# Chestnut_V2_0.net
KiCad netlist of a schematic drawn in EAGLE
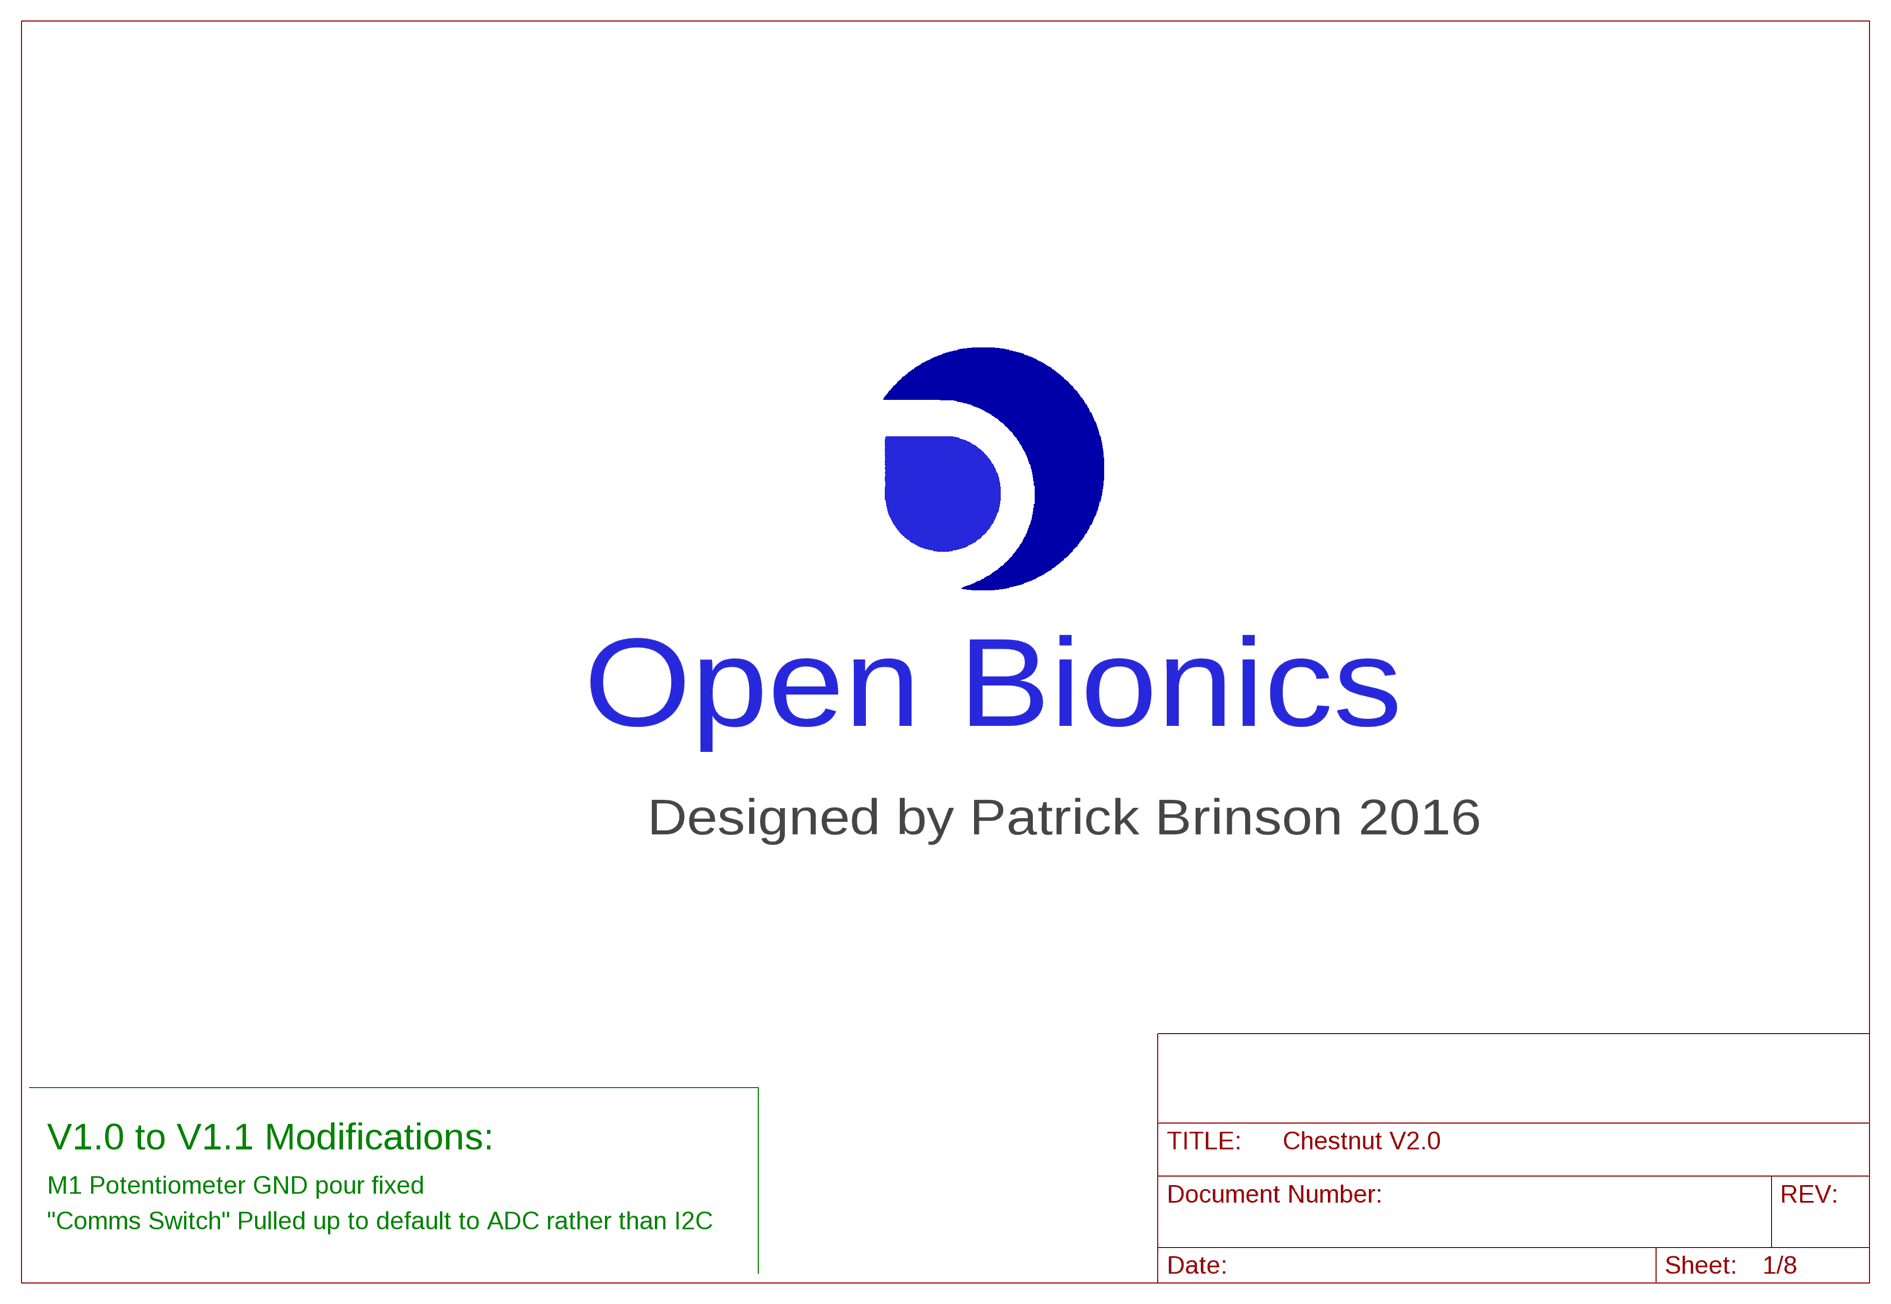
[diagram p0: schematic, sheet 1]
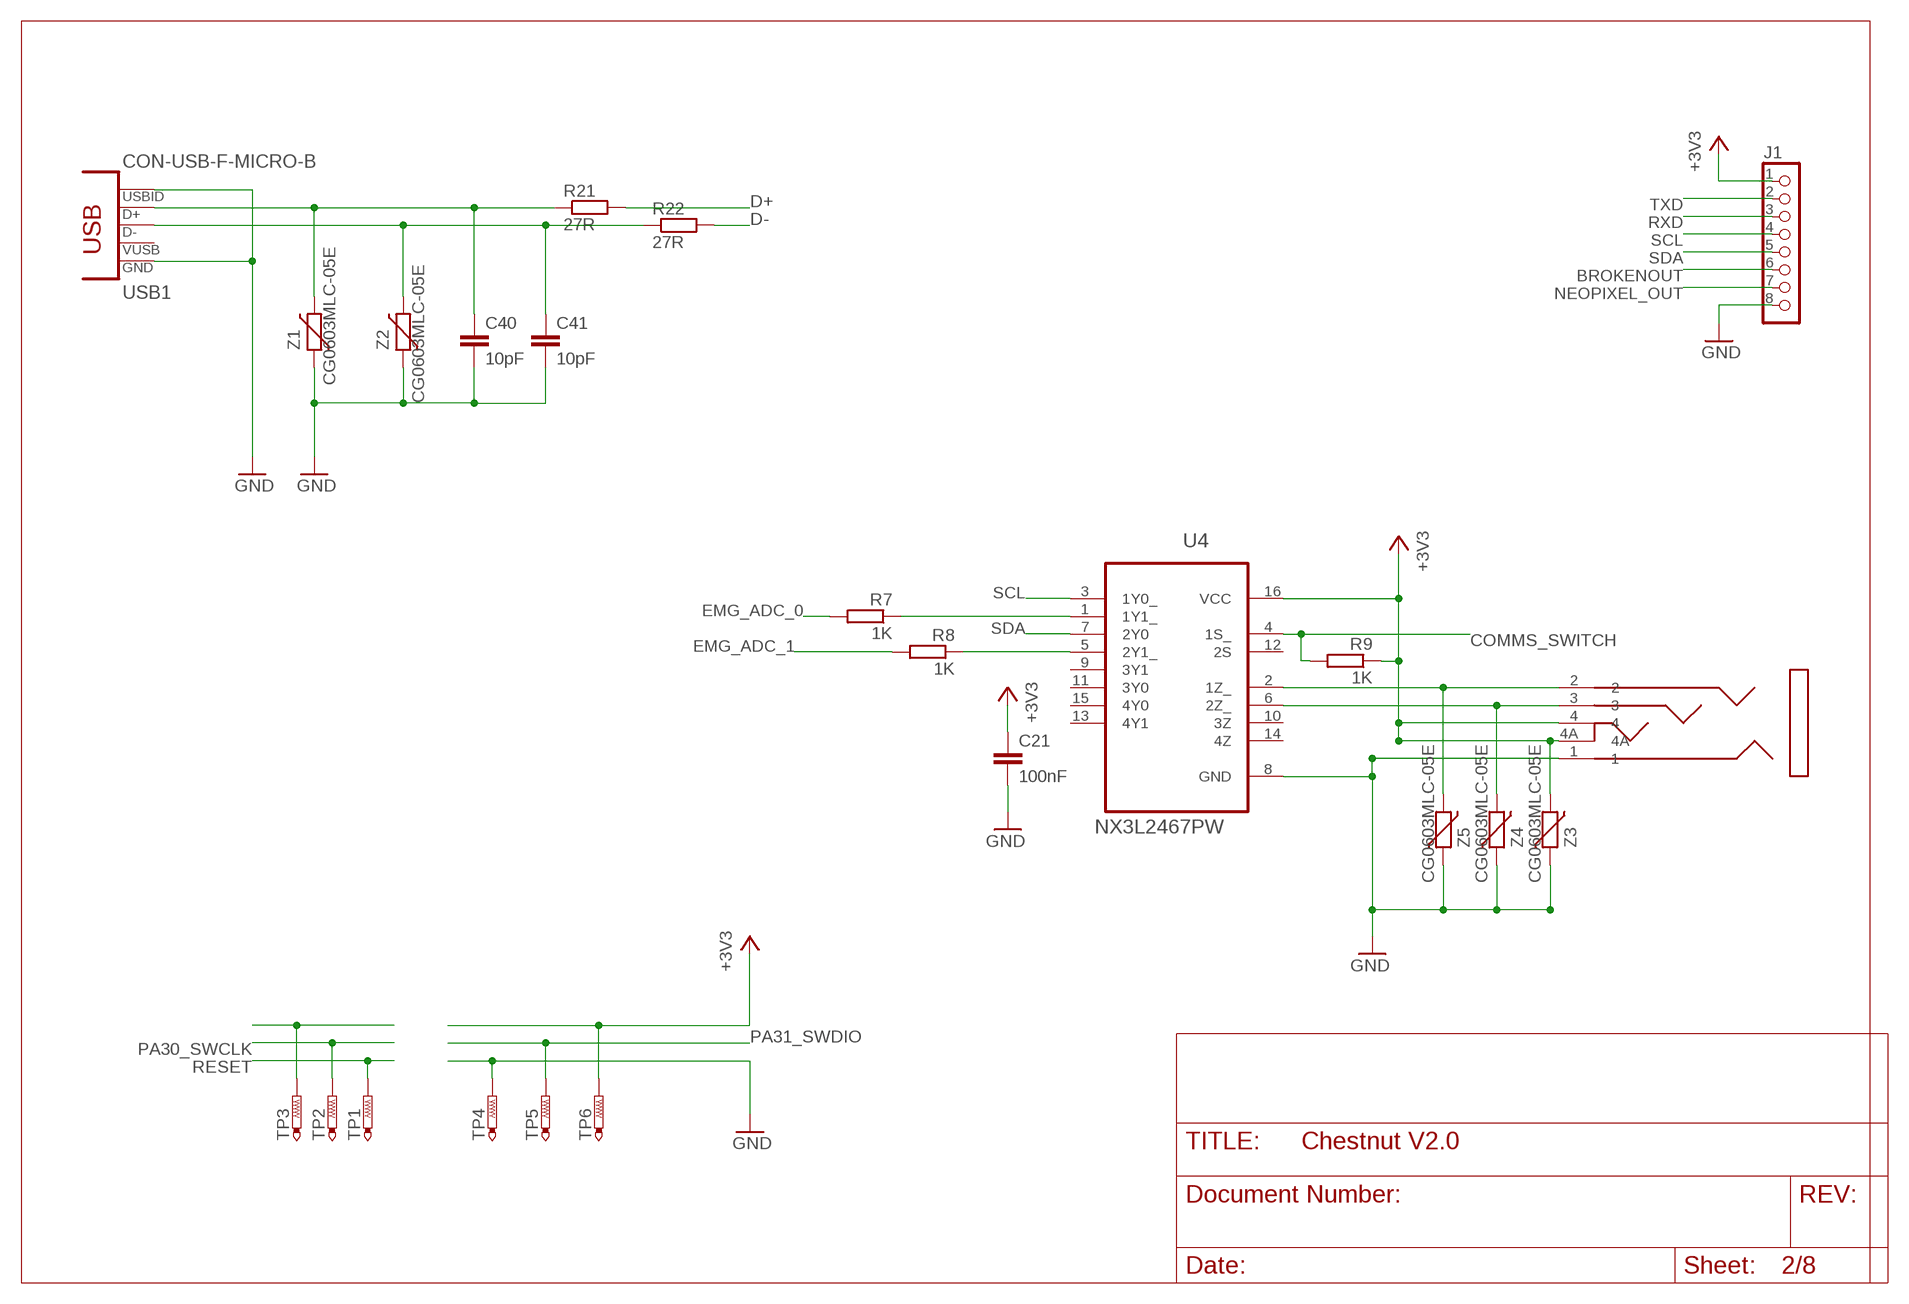
[diagram p1: schematic, sheet 2]
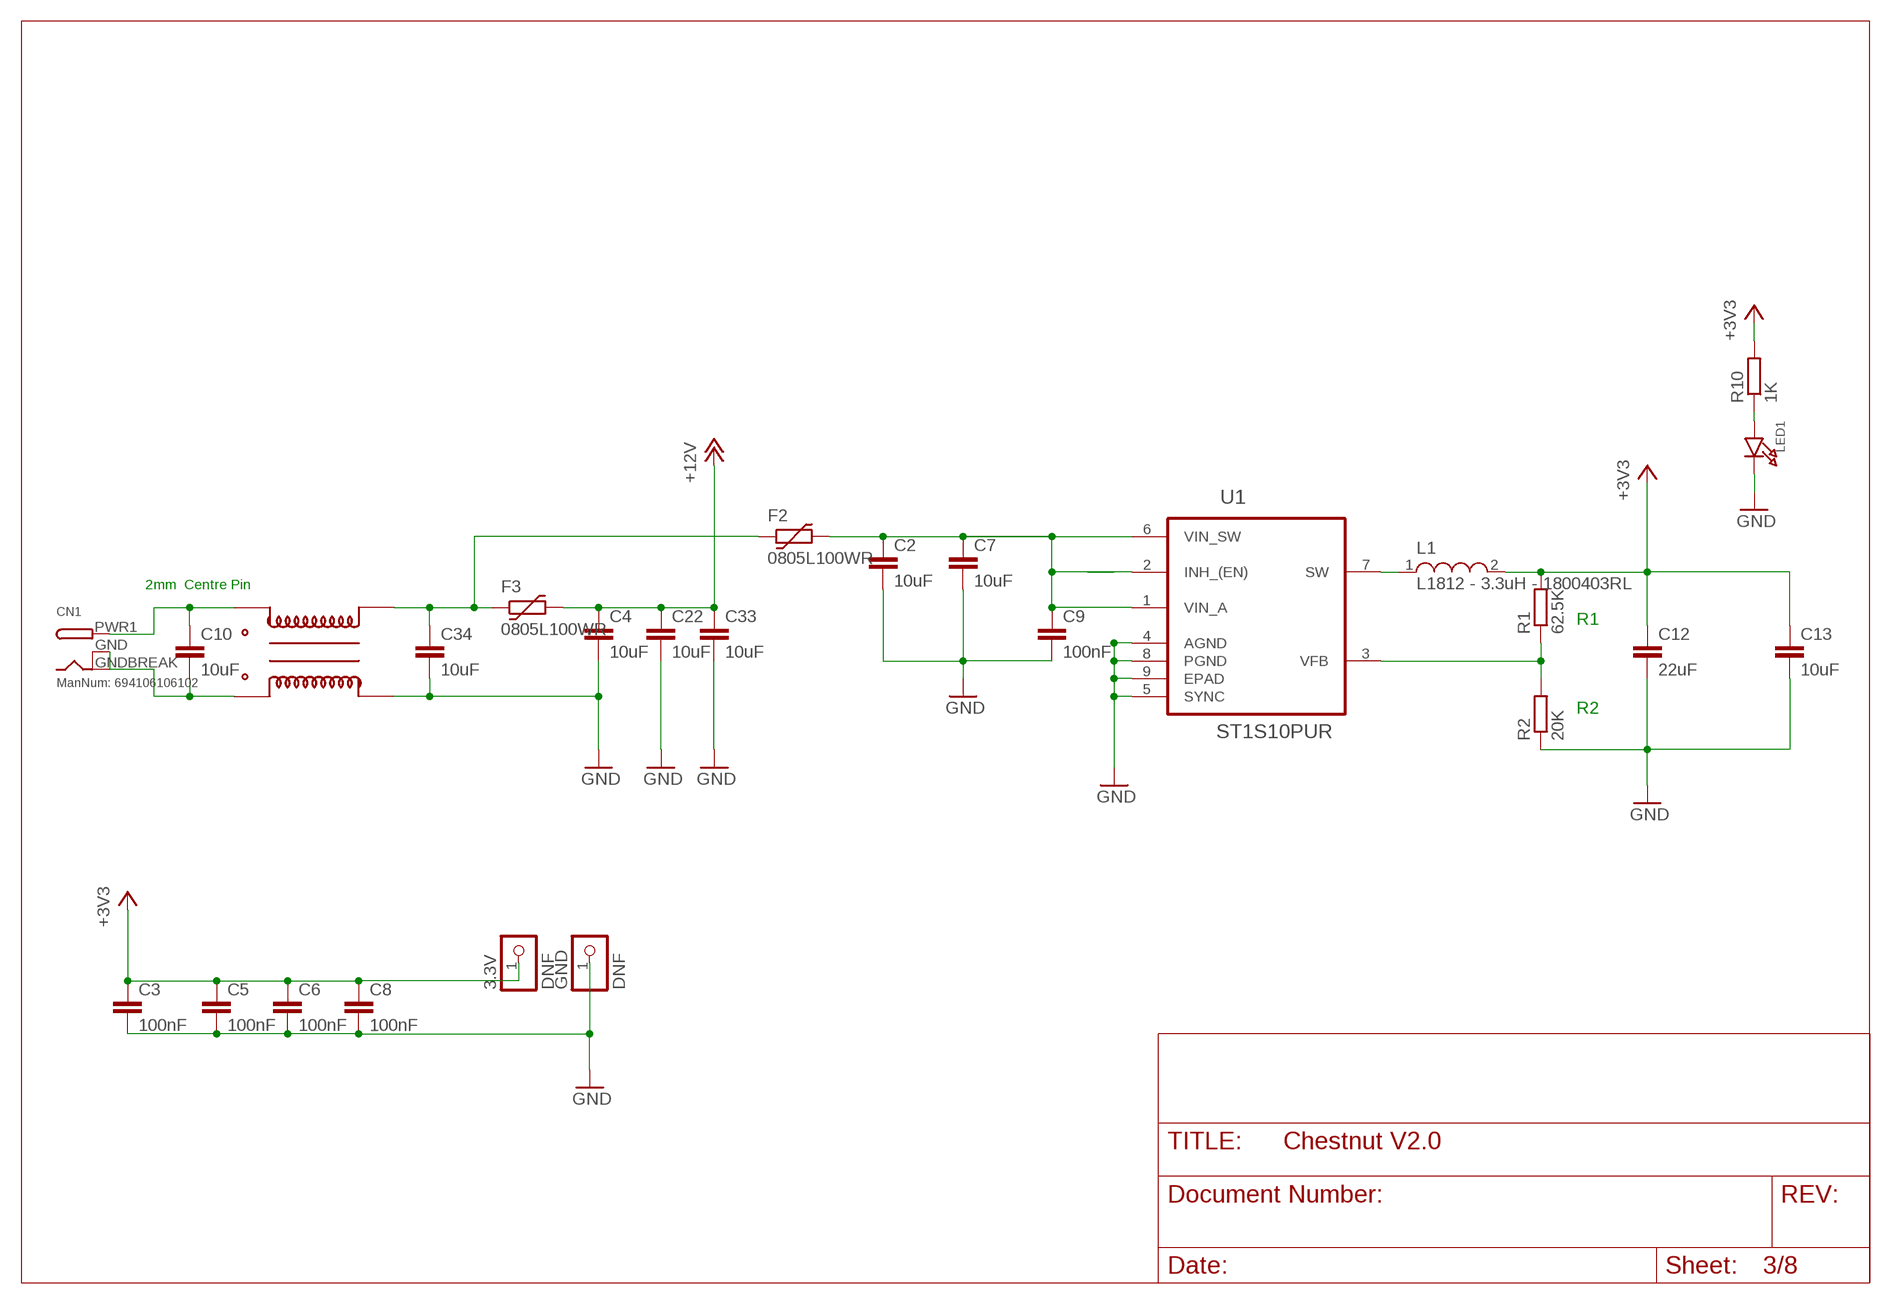
[diagram p2: schematic, sheet 3]
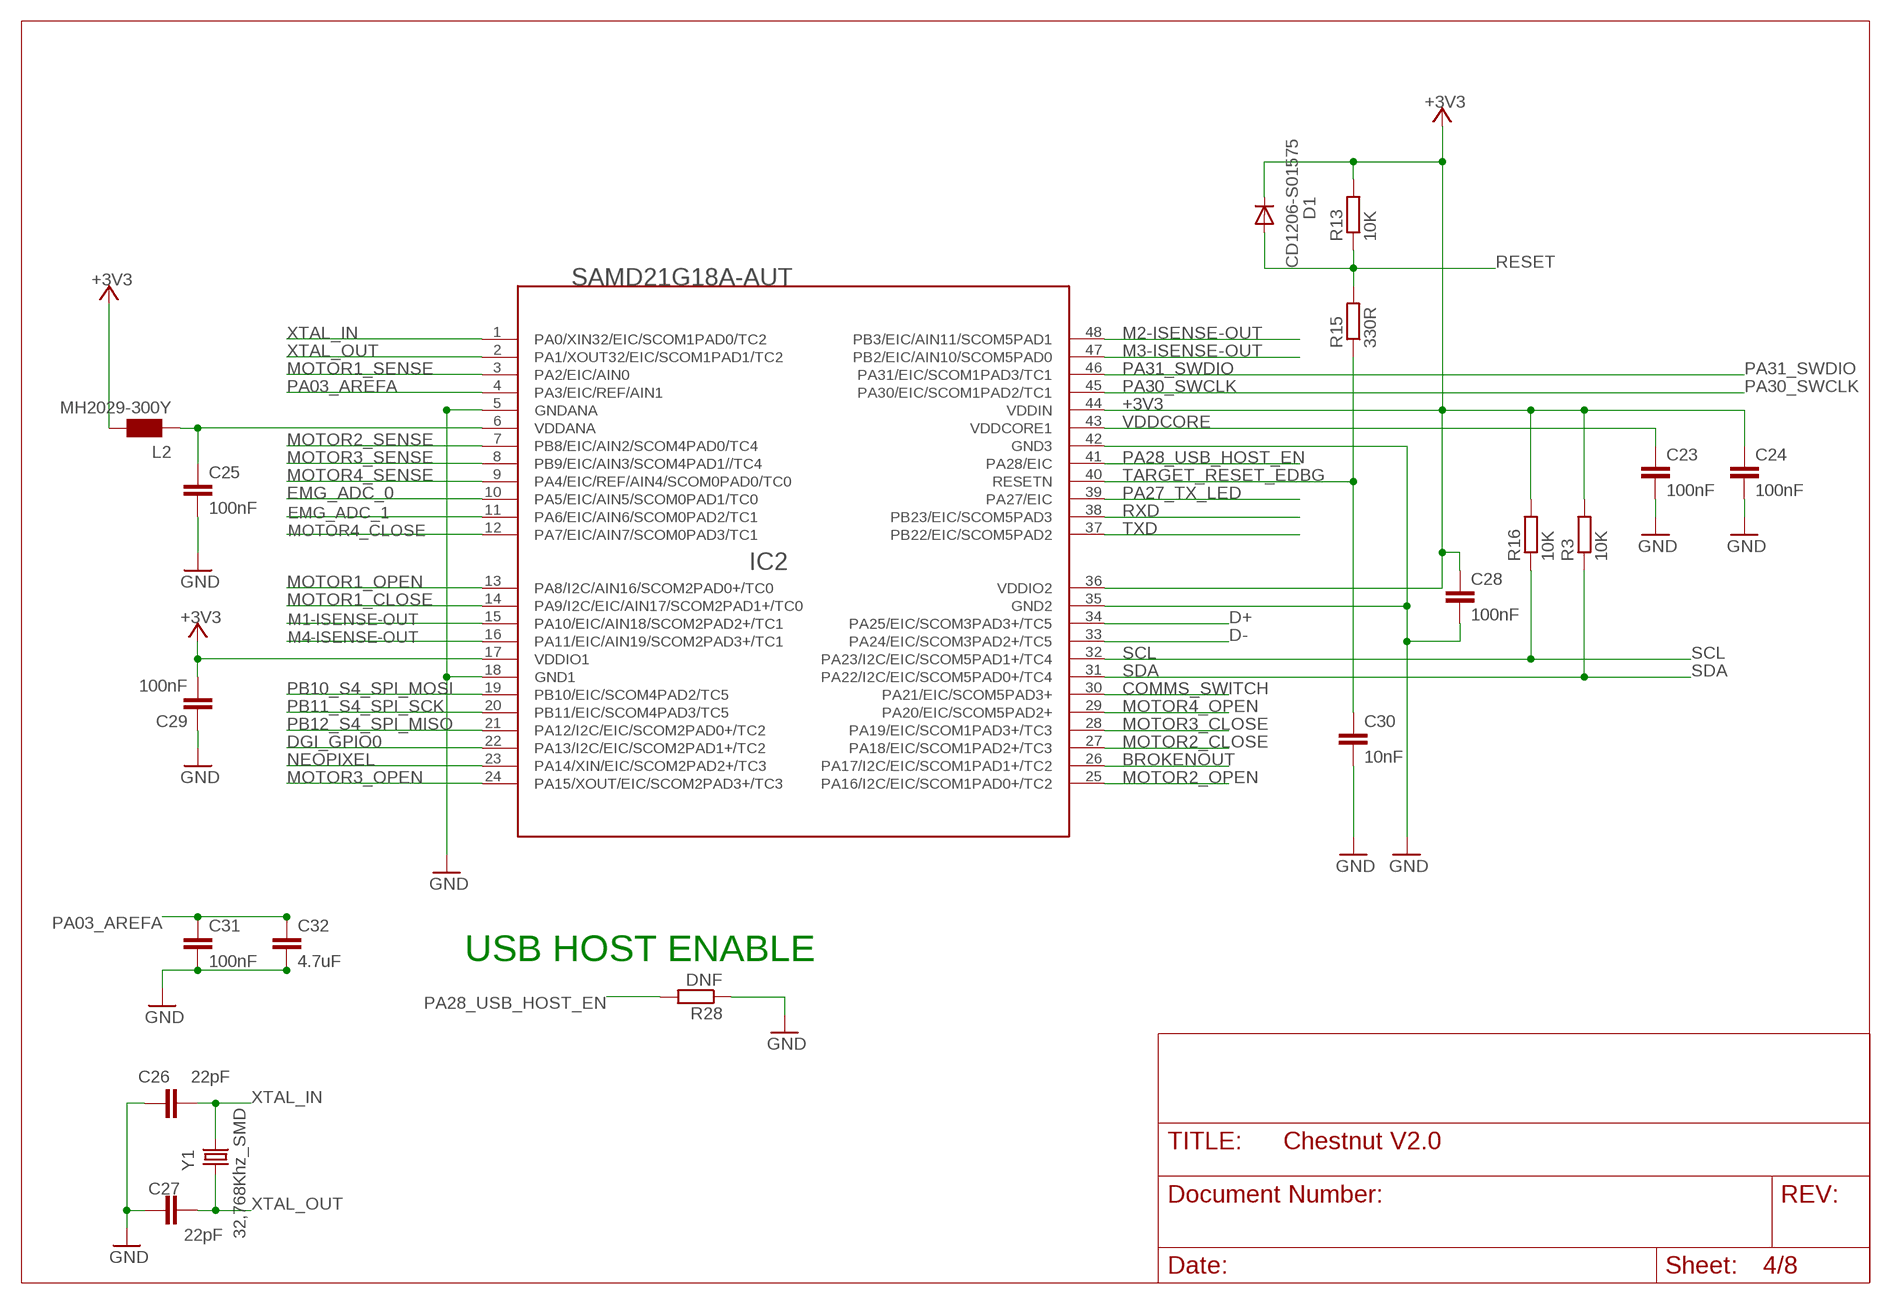
[diagram p3: schematic, sheet 4]
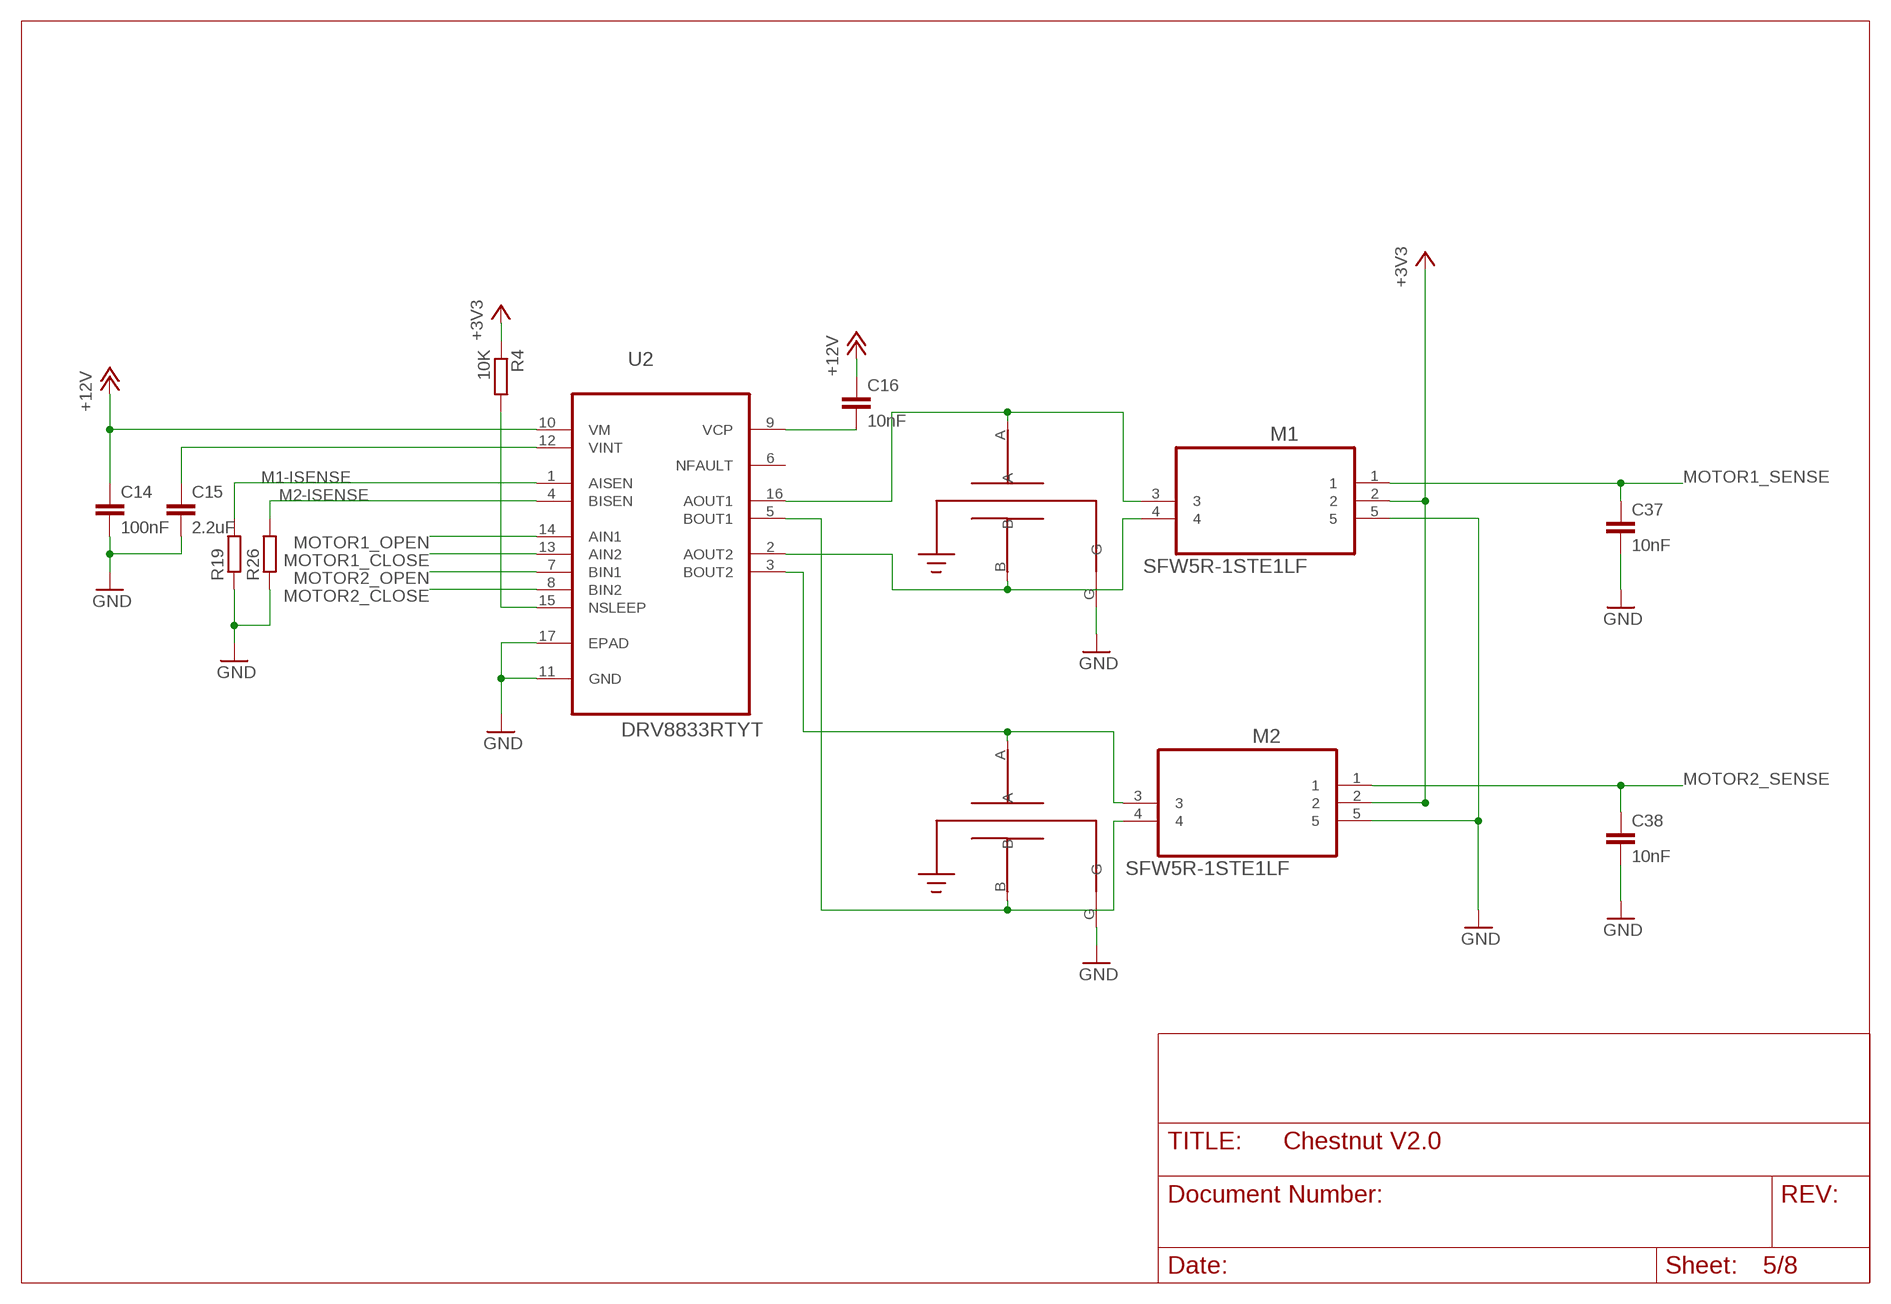
[diagram p4: schematic, sheet 5]
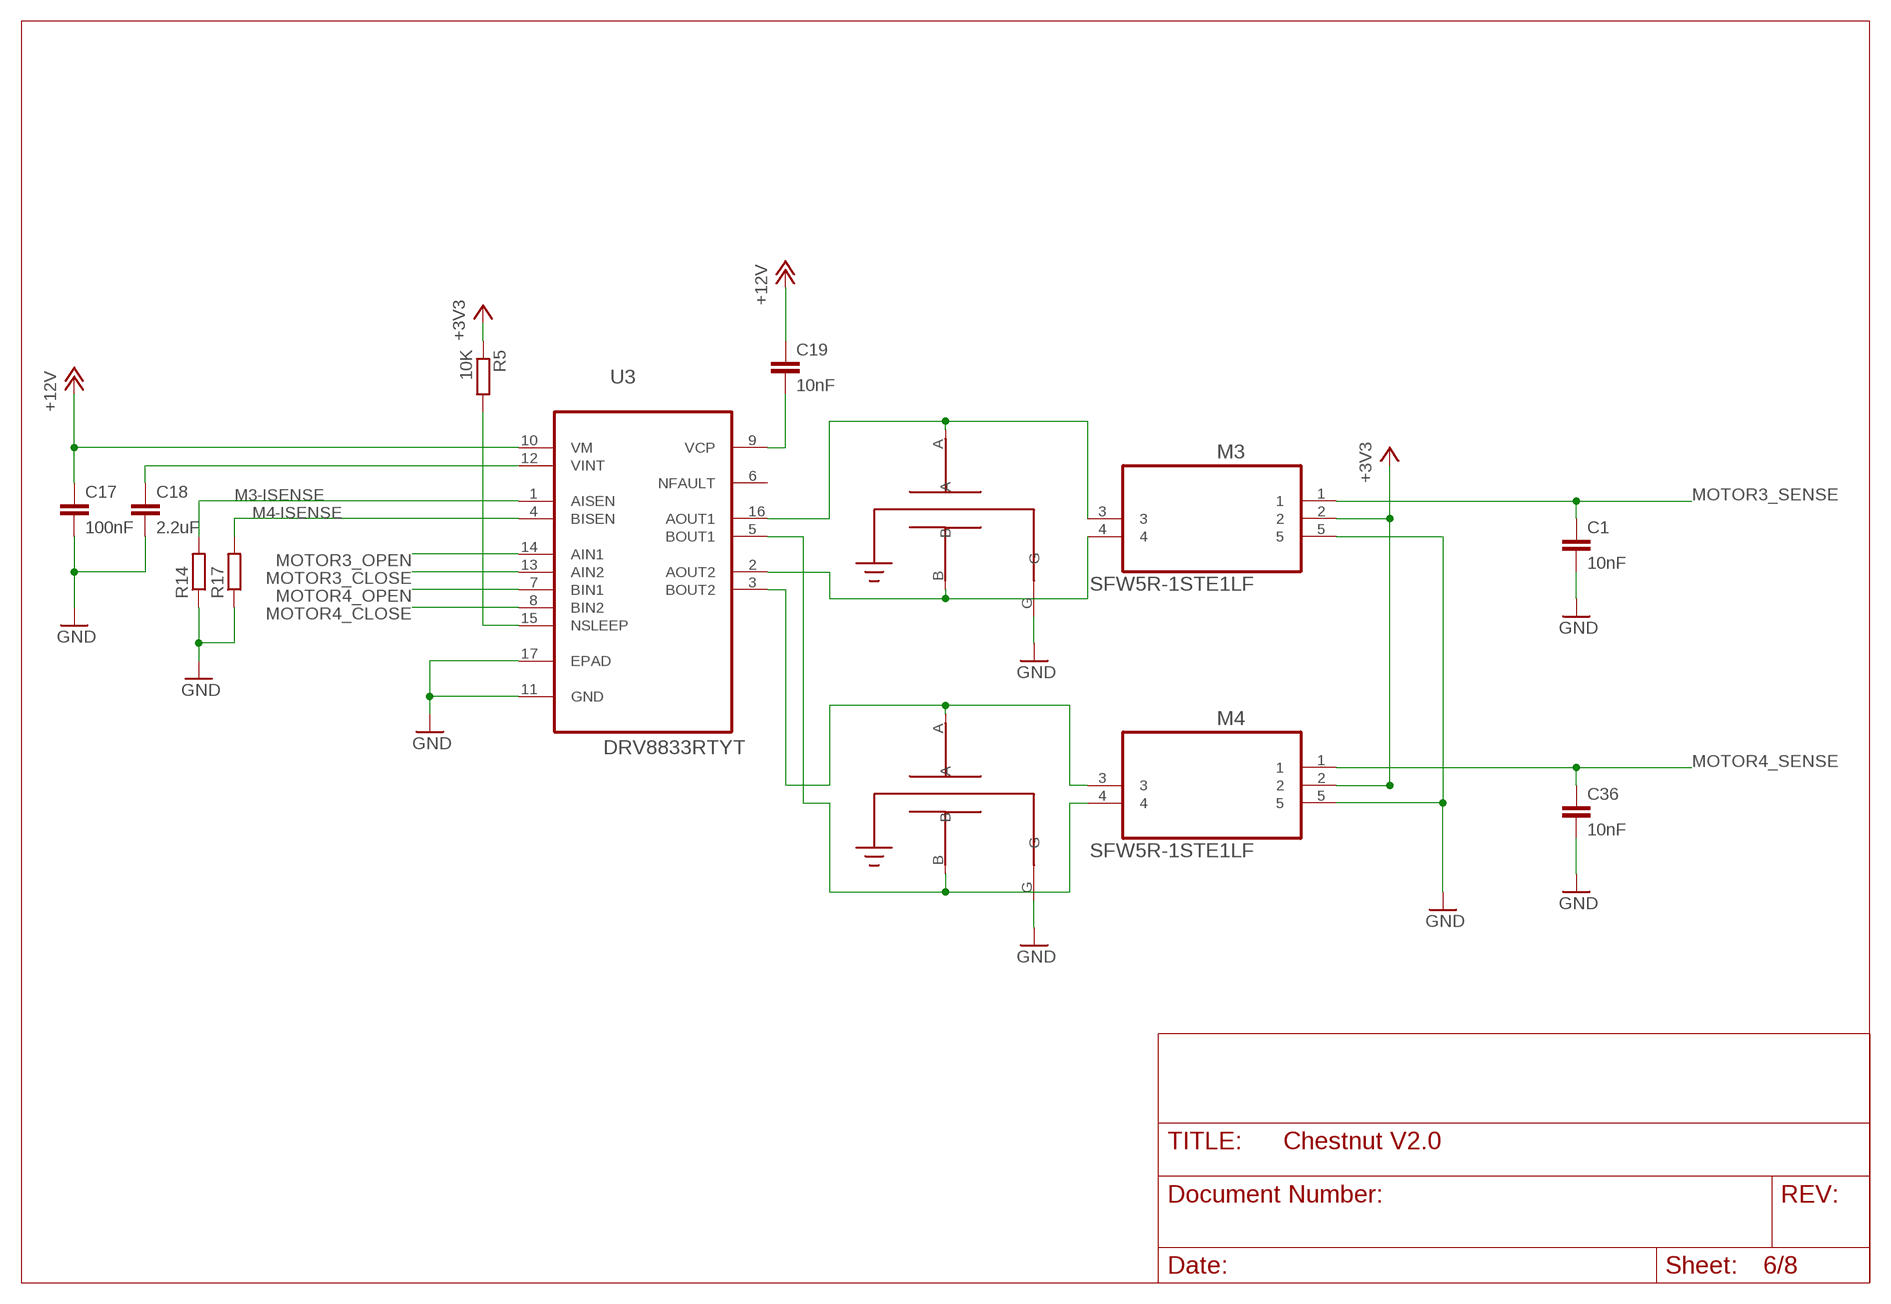
[diagram p5: schematic, sheet 6]
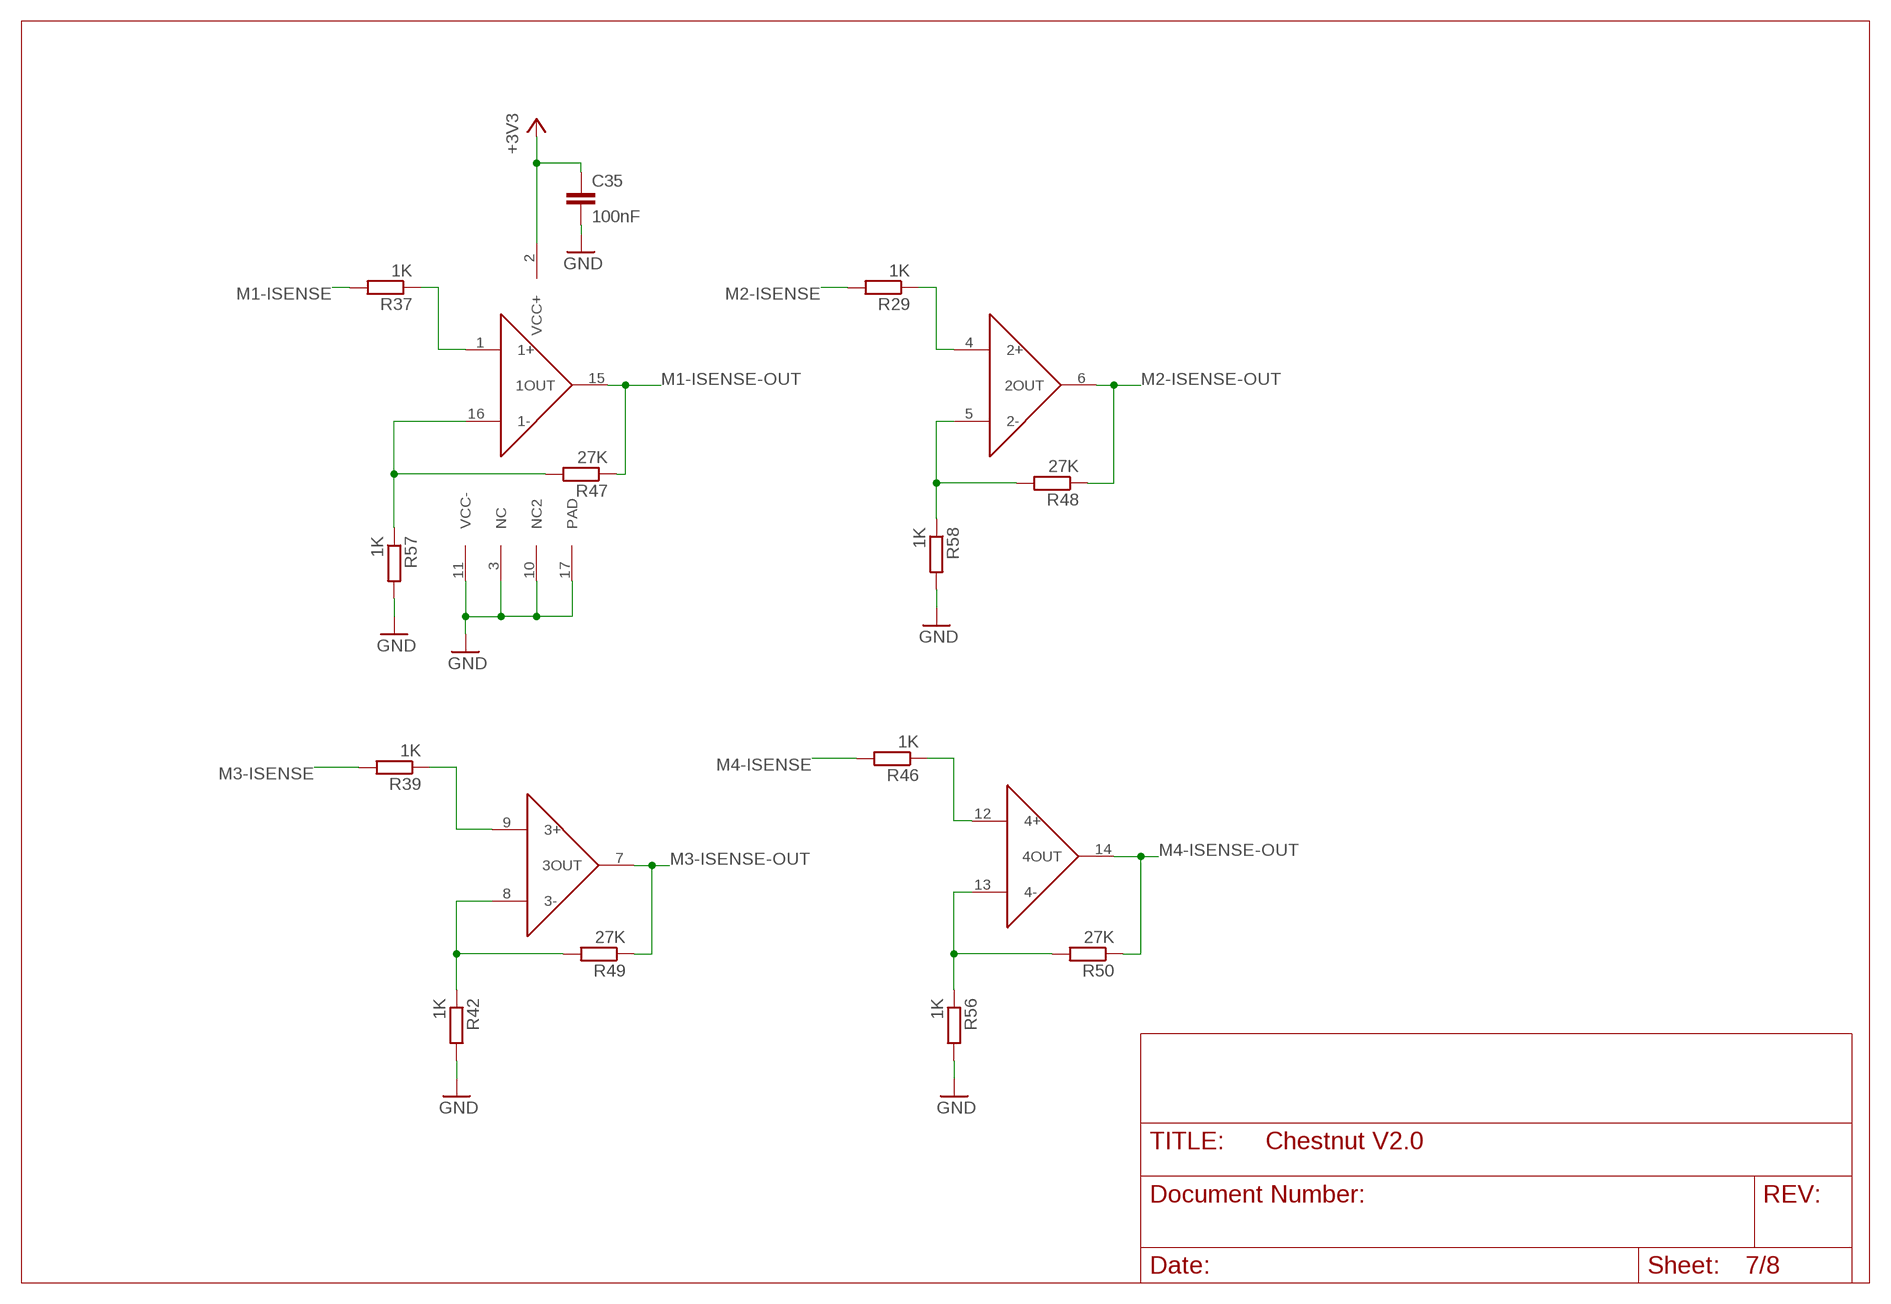
[diagram p6: schematic, sheet 7]
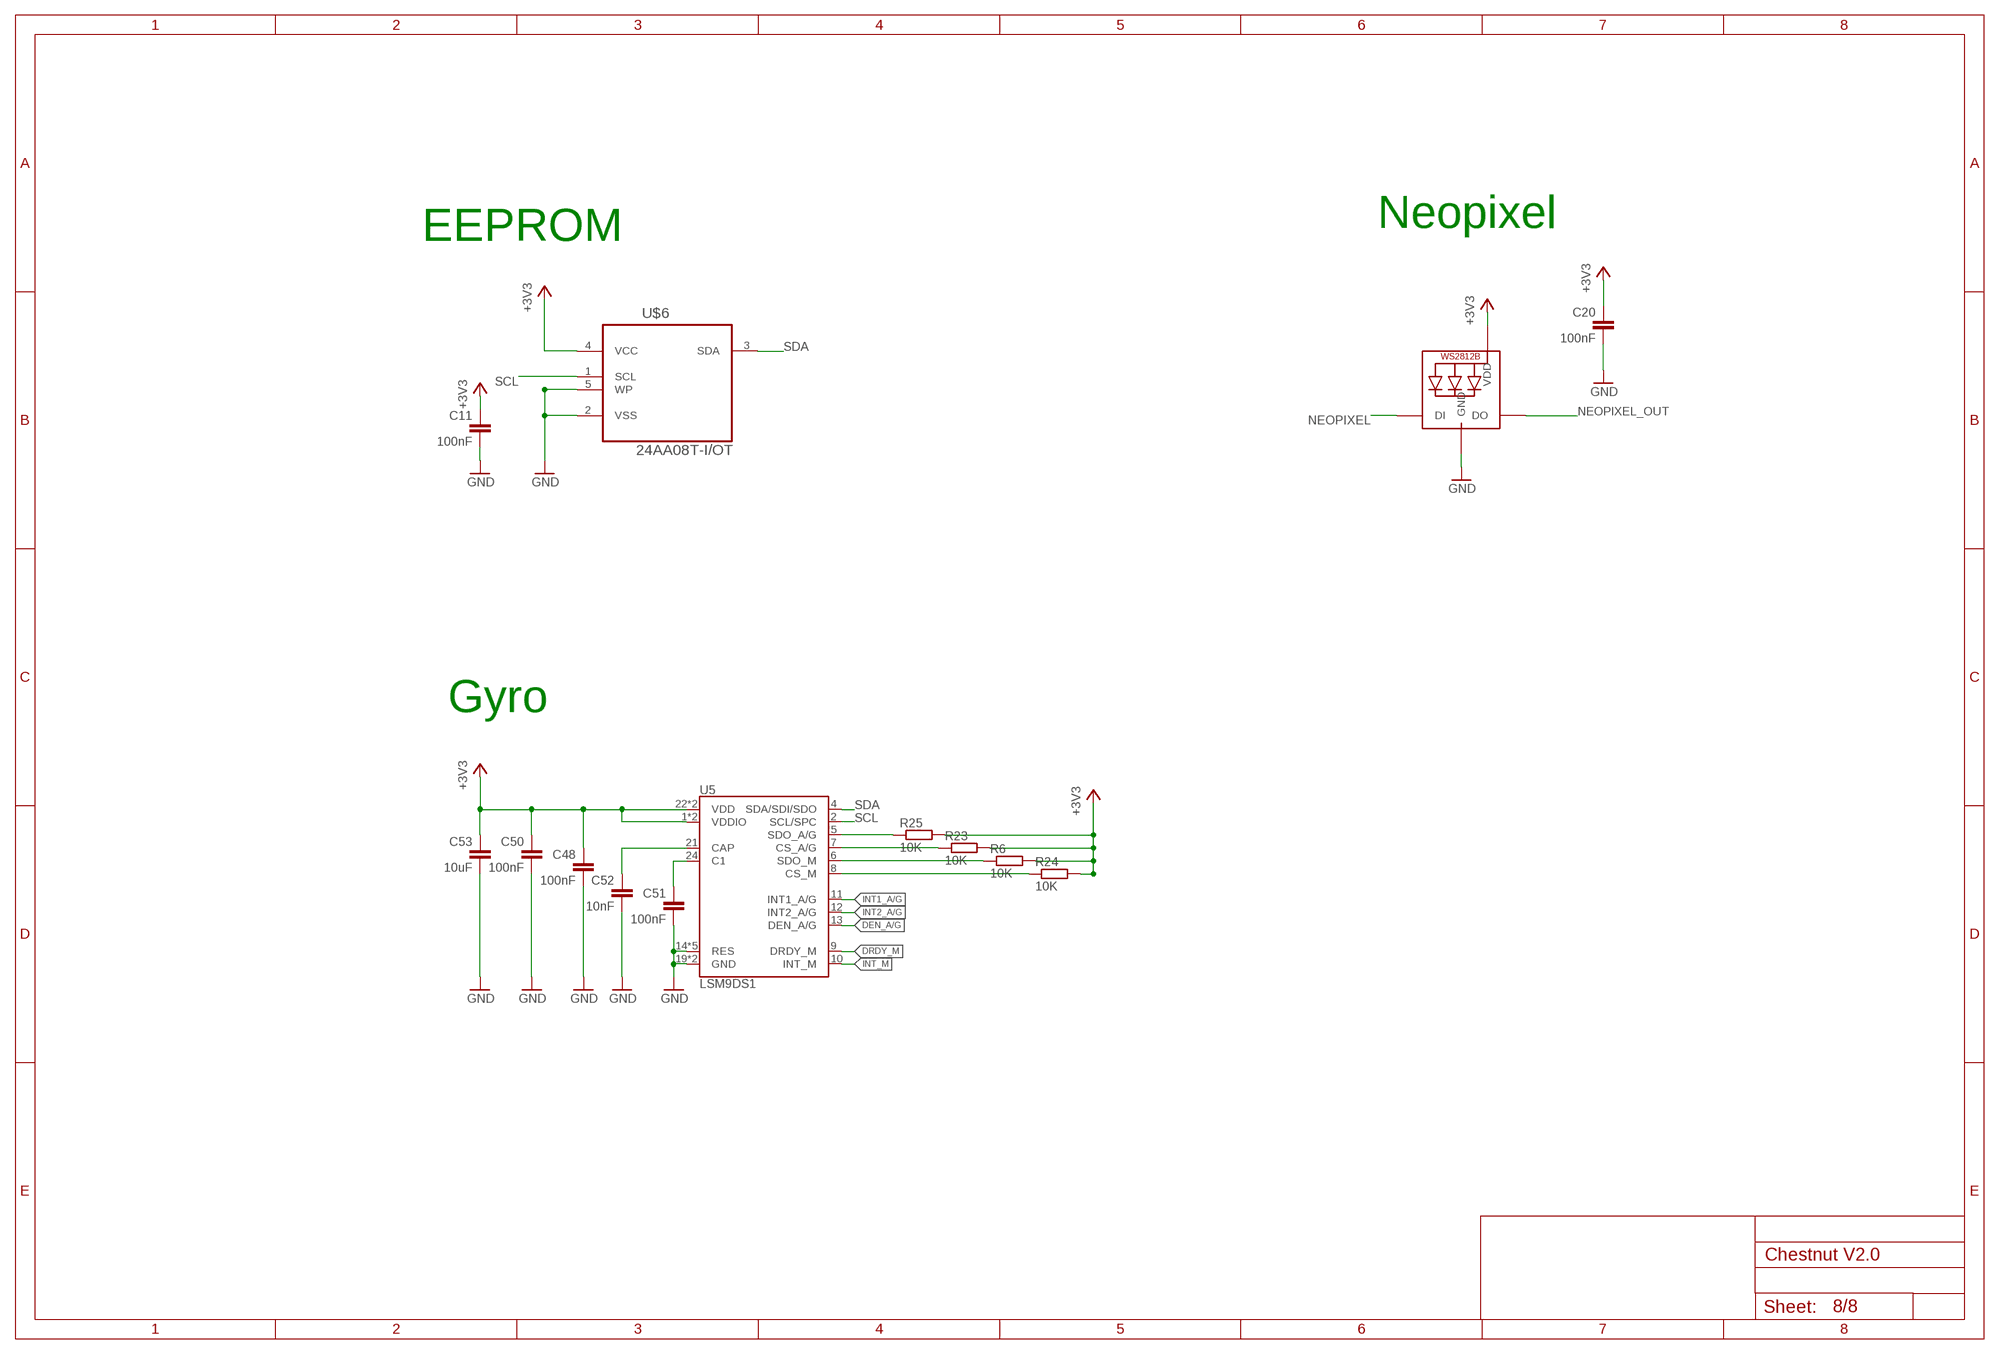
[diagram p7: schematic, sheet 8]

(export (version "E")
  (design (tool "Eeschema 10.0.6"))
  (components
    (comp (ref "C11")
      (value "100nF")
      (footprint "eagle-import:C0402")
      (libsource (lib "eagle-import") (part "C-EUC0402"))
    )
    (comp (ref "C20")
      (value "100nF")
      (footprint "eagle-import:C0402")
      (libsource (lib "eagle-import") (part "C-EUC0402"))
    )
    (comp (ref "C48")
      (value "100nF")
      (footprint "eagle-import:C0402")
      (libsource (lib "eagle-import") (part "C-EUC0402"))
    )
    (comp (ref "C50")
      (value "100nF")
      (footprint "eagle-import:C0402")
      (libsource (lib "eagle-import") (part "C-EUC0402"))
    )
    (comp (ref "C51")
      (value "100nF")
      (footprint "eagle-import:C0402")
      (libsource (lib "eagle-import") (part "C-EUC0402"))
    )
    (comp (ref "C52")
      (value "10nF")
      (footprint "eagle-import:C0402")
      (libsource (lib "eagle-import") (part "C-EUC0402"))
    )
    (comp (ref "C53")
      (value "10uF")
      (footprint "eagle-import:C0805")
      (libsource (lib "eagle-import") (part "C-EUC0805"))
    )
    (comp (ref "LED2")
      (value "WS2812B3535")
      (footprint "eagle-import:LED3535")
      (libsource (lib "eagle-import") (part "WS2812B3535"))
    )
    (comp (ref "R6")
      (value "10K")
      (footprint "eagle-import:R0402")
      (libsource (lib "eagle-import") (part "R-EU_R0402"))
    )
    (comp (ref "R23")
      (value "10K")
      (footprint "eagle-import:R0402")
      (libsource (lib "eagle-import") (part "R-EU_R0402"))
    )
    (comp (ref "R24")
      (value "10K")
      (footprint "eagle-import:R0402")
      (libsource (lib "eagle-import") (part "R-EU_R0402"))
    )
    (comp (ref "R25")
      (value "10K")
      (footprint "eagle-import:R0402")
      (libsource (lib "eagle-import") (part "R-EU_R0402"))
    )
    (comp (ref "U$6")
      (value "24AA08T-I/OT")
      (footprint "eagle-import:SOT95P290X145-5N")
      (libsource (lib "eagle-import") (part "24AA08T-I/OT"))
    )
    (comp (ref "U5")
      (value "LSM9DS1")
      (footprint "eagle-import:LGA24-8X4")
      (libsource (lib "eagle-import") (part "LSM9DS1"))
    )
    (comp (ref "C35")
      (value "100nF")
      (footprint "eagle-import:C0402")
      (libsource (lib "eagle-import") (part "C-EUC0402"))
    )
    (comp (ref "R29")
      (value "1K")
      (footprint "eagle-import:R0402")
      (libsource (lib "eagle-import") (part "R-EU_R0402"))
    )
    (comp (ref "R37")
      (value "1K")
      (footprint "eagle-import:R0402")
      (libsource (lib "eagle-import") (part "R-EU_R0402"))
    )
    (comp (ref "R39")
      (value "1K")
      (footprint "eagle-import:R0402")
      (libsource (lib "eagle-import") (part "R-EU_R0402"))
    )
    (comp (ref "R42")
      (value "1K")
      (footprint "eagle-import:R0402")
      (libsource (lib "eagle-import") (part "R-EU_R0402"))
    )
    (comp (ref "R46")
      (value "1K")
      (footprint "eagle-import:R0402")
      (libsource (lib "eagle-import") (part "R-EU_R0402"))
    )
    (comp (ref "R47")
      (value "27K")
      (footprint "eagle-import:R0402")
      (libsource (lib "eagle-import") (part "R-EU_R0402"))
    )
    (comp (ref "R48")
      (value "27K")
      (footprint "eagle-import:R0402")
      (libsource (lib "eagle-import") (part "R-EU_R0402"))
    )
    (comp (ref "R49")
      (value "27K")
      (footprint "eagle-import:R0402")
      (libsource (lib "eagle-import") (part "R-EU_R0402"))
    )
    (comp (ref "R50")
      (value "27K")
      (footprint "eagle-import:R0402")
      (libsource (lib "eagle-import") (part "R-EU_R0402"))
    )
    (comp (ref "R56")
      (value "1K")
      (footprint "eagle-import:R0402")
      (libsource (lib "eagle-import") (part "R-EU_R0402"))
    )
    (comp (ref "R57")
      (value "1K")
      (footprint "eagle-import:R0402")
      (libsource (lib "eagle-import") (part "R-EU_R0402"))
    )
    (comp (ref "R58")
      (value "1K")
      (footprint "eagle-import:R0402")
      (libsource (lib "eagle-import") (part "R-EU_R0402"))
    )
    (comp (ref "U$15")
      (value "TSZ124IQ4T")
      (footprint "eagle-import:TSZ124IQ4T")
      (libsource (lib "eagle-import") (part "TSZ124IQ4T"))
    )
    (comp (ref "3.3V")
      (value "DNF")
      (footprint "eagle-import:1X01_ROUND")
      (libsource (lib "eagle-import") (part "HEADER-1X1ROUND"))
    )
    (comp (ref "C2")
      (value "10uF")
      (footprint "eagle-import:C0805")
      (libsource (lib "eagle-import") (part "C-EUC0805"))
    )
    (comp (ref "C3")
      (value "100nF")
      (footprint "eagle-import:C0402")
      (libsource (lib "eagle-import") (part "C-EUC0402"))
    )
    (comp (ref "C4")
      (value "10uF")
      (footprint "eagle-import:C0805")
      (libsource (lib "eagle-import") (part "C-EUC0805"))
    )
    (comp (ref "C5")
      (value "100nF")
      (footprint "eagle-import:C0402")
      (libsource (lib "eagle-import") (part "C-EUC0402"))
    )
    (comp (ref "C6")
      (value "100nF")
      (footprint "eagle-import:C0402")
      (libsource (lib "eagle-import") (part "C-EUC0402"))
    )
    (comp (ref "C7")
      (value "10uF")
      (footprint "eagle-import:C0805")
      (libsource (lib "eagle-import") (part "C-EUC0805"))
    )
    (comp (ref "C8")
      (value "100nF")
      (footprint "eagle-import:C0402")
      (libsource (lib "eagle-import") (part "C-EUC0402"))
    )
    (comp (ref "C9")
      (value "100nF")
      (footprint "eagle-import:C0402")
      (libsource (lib "eagle-import") (part "C-EUC0402"))
    )
    (comp (ref "C10")
      (value "10uF")
      (footprint "eagle-import:C0805")
      (libsource (lib "eagle-import") (part "C-EUC0805"))
    )
    (comp (ref "C12")
      (value "22uF")
      (footprint "eagle-import:C1210")
      (libsource (lib "eagle-import") (part "C-EUC1210"))
    )
    (comp (ref "C13")
      (value "10uF")
      (footprint "eagle-import:C0805")
      (libsource (lib "eagle-import") (part "C-EUC0805"))
    )
    (comp (ref "C22")
      (value "10uF")
      (footprint "eagle-import:C0805")
      (libsource (lib "eagle-import") (part "C-EUC0805"))
    )
    (comp (ref "C33")
      (value "10uF")
      (footprint "eagle-import:C0805")
      (libsource (lib "eagle-import") (part "C-EUC0805"))
    )
    (comp (ref "C34")
      (value "10uF")
      (footprint "eagle-import:C0805")
      (libsource (lib "eagle-import") (part "C-EUC0805"))
    )
    (comp (ref "CN1")
      (value "ManNum: 694106106102")
      (footprint "eagle-import:DCJACK_2MM_SMT")
      (libsource (lib "eagle-import") (part "DCBARRELSMT"))
    )
    (comp (ref "F2")
      (value "0805L100WR")
      (footprint "eagle-import:PTC0805")
      (libsource (lib "eagle-import") (part "FUSE_PTC-0805"))
    )
    (comp (ref "F3")
      (value "0805L100WR")
      (footprint "eagle-import:PTC0805")
      (libsource (lib "eagle-import") (part "FUSE_PTC-0805"))
    )
    (comp (ref "GND")
      (value "DNF")
      (footprint "eagle-import:1X01_ROUND")
      (libsource (lib "eagle-import") (part "HEADER-1X1ROUND"))
    )
    (comp (ref "L1")
      (value "L1812 - 3.3uH - 1800403RL")
      (footprint "eagle-import:L1812")
      (libsource (lib "eagle-import") (part "INDUCTOR-L1812"))
    )
    (comp (ref "LED1")
      (value "LED0603")
      (footprint "eagle-import:CHIPLED_0603")
      (libsource (lib "eagle-import") (part "LED0603"))
    )
    (comp (ref "R1")
      (value "62.5K")
      (footprint "eagle-import:R0603")
      (libsource (lib "eagle-import") (part "R-EU_R0603"))
    )
    (comp (ref "R2")
      (value "20K")
      (footprint "eagle-import:R0603")
      (libsource (lib "eagle-import") (part "R-EU_R0603"))
    )
    (comp (ref "R10")
      (value "1K")
      (footprint "eagle-import:R0402")
      (libsource (lib "eagle-import") (part "R-EU_R0402"))
    )
    (comp (ref "U$5")
      (value "DLW5BTN501SQ2L")
      (footprint "eagle-import:DLW5BTN501SQ2L")
      (libsource (lib "eagle-import") (part "DLW5BTN501SQ2L"))
    )
    (comp (ref "U1")
      (value "ST1S10PUR")
      (footprint "eagle-import:DFN400X400X100-9N")
      (libsource (lib "eagle-import") (part "ST1S10PUR"))
    )
    (comp (ref "C21")
      (value "100nF")
      (footprint "eagle-import:C0402")
      (libsource (lib "eagle-import") (part "C-EUC0402"))
    )
    (comp (ref "C40")
      (value "10pF")
      (footprint "eagle-import:C0402")
      (libsource (lib "eagle-import") (part "C-EUC0402"))
    )
    (comp (ref "C41")
      (value "10pF")
      (footprint "eagle-import:C0402")
      (libsource (lib "eagle-import") (part "C-EUC0402"))
    )
    (comp (ref "J1")
      (value "CON_HEADER_1X08-PTH")
      (footprint "eagle-import:M1X8")
      (libsource (lib "eagle-import") (part "CON_HEADER_1X08-PTH"))
    )
    (comp (ref "R7")
      (value "1K")
      (footprint "eagle-import:R0402")
      (libsource (lib "eagle-import") (part "R-EU_R0402"))
    )
    (comp (ref "R8")
      (value "1K")
      (footprint "eagle-import:R0402")
      (libsource (lib "eagle-import") (part "R-EU_R0402"))
    )
    (comp (ref "R9")
      (value "1K")
      (footprint "eagle-import:R0402")
      (libsource (lib "eagle-import") (part "R-EU_R0402"))
    )
    (comp (ref "R21")
      (value "27R")
      (footprint "eagle-import:R0402")
      (libsource (lib "eagle-import") (part "R-EU_R0402"))
    )
    (comp (ref "R22")
      (value "27R")
      (footprint "eagle-import:R0402")
      (libsource (lib "eagle-import") (part "R-EU_R0402"))
    )
    (comp (ref "TP1")
      (value "PTR1TP11R")
      (footprint "eagle-import:TP11R")
      (libsource (lib "eagle-import") (part "PTR1TP11R"))
    )
    (comp (ref "TP2")
      (value "PTR1TP11R")
      (footprint "eagle-import:TP11R")
      (libsource (lib "eagle-import") (part "PTR1TP11R"))
    )
    (comp (ref "TP3")
      (value "PTR1TP11R")
      (footprint "eagle-import:TP11R")
      (libsource (lib "eagle-import") (part "PTR1TP11R"))
    )
    (comp (ref "TP4")
      (value "PTR1TP11R")
      (footprint "eagle-import:TP11R")
      (libsource (lib "eagle-import") (part "PTR1TP11R"))
    )
    (comp (ref "TP5")
      (value "PTR1TP11R")
      (footprint "eagle-import:TP11R")
      (libsource (lib "eagle-import") (part "PTR1TP11R"))
    )
    (comp (ref "TP6")
      (value "PTR1TP11R")
      (footprint "eagle-import:TP11R")
      (libsource (lib "eagle-import") (part "PTR1TP11R"))
    )
    (comp (ref "U$7")
      (value "LUMBERG_1503-13-VP3")
      (footprint "eagle-import:LUMBERG_1503-13-VP3")
      (libsource (lib "eagle-import") (part "LUMBERG_1503-13-VP3"))
    )
    (comp (ref "U4")
      (value "NX3L2467PW")
      (footprint "eagle-import:SOP65P640X110-16N")
      (libsource (lib "eagle-import") (part "NX3L2467PW"))
    )
    (comp (ref "USB1")
      (value "CON-USB-F-MICRO-B")
      (footprint "eagle-import:CONN_USB_MICRO-B")
      (libsource (lib "eagle-import") (part "CON-USB-F-MICRO-B"))
    )
    (comp (ref "Z1")
      (value "CG0603MLC-05E")
      (footprint "eagle-import:CT_CN0603")
      (libsource (lib "eagle-import") (part "VARISTORCN0603"))
    )
    (comp (ref "Z2")
      (value "CG0603MLC-05E")
      (footprint "eagle-import:CT_CN0603")
      (libsource (lib "eagle-import") (part "VARISTORCN0603"))
    )
    (comp (ref "Z3")
      (value "CG0603MLC-05E")
      (footprint "eagle-import:CT_CN0603")
      (libsource (lib "eagle-import") (part "VARISTORCN0603"))
    )
    (comp (ref "Z4")
      (value "CG0603MLC-05E")
      (footprint "eagle-import:CT_CN0603")
      (libsource (lib "eagle-import") (part "VARISTORCN0603"))
    )
    (comp (ref "Z5")
      (value "CG0603MLC-05E")
      (footprint "eagle-import:CT_CN0603")
      (libsource (lib "eagle-import") (part "VARISTORCN0603"))
    )
    (comp (ref "C23")
      (value "100nF")
      (footprint "eagle-import:C0402")
      (libsource (lib "eagle-import") (part "C-EUC0402"))
    )
    (comp (ref "C24")
      (value "100nF")
      (footprint "eagle-import:C0402")
      (libsource (lib "eagle-import") (part "C-EUC0402"))
    )
    (comp (ref "C25")
      (value "100nF")
      (footprint "eagle-import:C0402")
      (libsource (lib "eagle-import") (part "C-EUC0402"))
    )
    (comp (ref "C26")
      (value "22pF")
      (footprint "eagle-import:C0402")
      (libsource (lib "eagle-import") (part "C-EUC0402"))
    )
    (comp (ref "C27")
      (value "22pF")
      (footprint "eagle-import:C0402")
      (libsource (lib "eagle-import") (part "C-EUC0402"))
    )
    (comp (ref "C28")
      (value "100nF")
      (footprint "eagle-import:C0402")
      (libsource (lib "eagle-import") (part "C-EUC0402"))
    )
    (comp (ref "C29")
      (value "100nF")
      (footprint "eagle-import:C0402")
      (libsource (lib "eagle-import") (part "C-EUC0402"))
    )
    (comp (ref "C30")
      (value "10nF")
      (footprint "eagle-import:C0402")
      (libsource (lib "eagle-import") (part "C-EUC0402"))
    )
    (comp (ref "C31")
      (value "100nF")
      (footprint "eagle-import:C0402")
      (libsource (lib "eagle-import") (part "C-EUC0402"))
    )
    (comp (ref "C32")
      (value "4.7uF")
      (footprint "eagle-import:C0603")
      (libsource (lib "eagle-import") (part "C-EUC0603"))
    )
    (comp (ref "D1")
      (value "CD1206-S01575")
      (footprint "eagle-import:MINIMELF")
      (libsource (lib "eagle-import") (part "0012_CD1206-S01575"))
    )
    (comp (ref "IC2")
      (value "SAMD21G18A-AUT")
      (footprint "eagle-import:INTEGRATEDCIRCUITS_TQFP48-7X7")
      (libsource (lib "eagle-import") (part "INTEGRATEDCIRCUITS_1792_SAMD21G18A-AUT"))
    )
    (comp (ref "L2")
      (value "MH2029-300Y")
      (footprint "eagle-import:0805")
      (fields (field (name "PART_NUMBER") "BLM21PG300SN1D_/_MH2029-300Y"))
      (libsource (lib "eagle-import") (part "0001_BLM21PG300SN1D_/_MH2029-300Y"))
    )
    (comp (ref "R3")
      (value "10K")
      (footprint "eagle-import:R0402")
      (libsource (lib "eagle-import") (part "R-EU_R0402"))
    )
    (comp (ref "R13")
      (value "10K")
      (footprint "eagle-import:R0402")
      (libsource (lib "eagle-import") (part "R-EU_R0402"))
    )
    (comp (ref "R15")
      (value "330R")
      (footprint "eagle-import:R0402")
      (libsource (lib "eagle-import") (part "R-EU_R0402"))
    )
    (comp (ref "R16")
      (value "10K")
      (footprint "eagle-import:R0402")
      (libsource (lib "eagle-import") (part "R-EU_R0402"))
    )
    (comp (ref "R28")
      (value "DNF")
      (footprint "eagle-import:R0402")
      (libsource (lib "eagle-import") (part "R-EU_R0402"))
    )
    (comp (ref "Y1")
      (value "32,768Khz_SMD")
      (footprint "eagle-import:RESONATOR_EPSON_FC_145")
      (fields (field (name "PART_NUMBER") "ABS07-32.768KHZ-T"))
      (libsource (lib "eagle-import") (part "0213_ABS07-32.768KHZ-T"))
    )
    (comp (ref "C14")
      (value "100nF")
      (footprint "eagle-import:C0402")
      (libsource (lib "eagle-import") (part "C-EUC0402"))
    )
    (comp (ref "C15")
      (value "2.2uF")
      (footprint "eagle-import:C0603")
      (libsource (lib "eagle-import") (part "C-EUC0603"))
    )
    (comp (ref "C16")
      (value "10nF")
      (footprint "eagle-import:C0402")
      (libsource (lib "eagle-import") (part "C-EUC0402"))
    )
    (comp (ref "C37")
      (value "10nF")
      (footprint "eagle-import:C0402")
      (libsource (lib "eagle-import") (part "C-EUC0402"))
    )
    (comp (ref "C38")
      (value "10nF")
      (footprint "eagle-import:C0402")
      (libsource (lib "eagle-import") (part "C-EUC0402"))
    )
    (comp (ref "M1")
      (value "SFW5R-1STE1LF")
      (footprint "eagle-import:FCI_SFW5R-1STE1LF")
      (libsource (lib "eagle-import") (part "SFW5R-1STE1LF"))
    )
    (comp (ref "M2")
      (value "SFW5R-1STE1LF")
      (footprint "eagle-import:FCI_SFW5R-1STE1LF")
      (libsource (lib "eagle-import") (part "SFW5R-1STE1LF"))
    )
    (comp (ref "R4")
      (value "10K")
      (footprint "eagle-import:R0402")
      (libsource (lib "eagle-import") (part "R-EU_R0402"))
    )
    (comp (ref "R19")
      (value "R-EU_R0805")
      (footprint "eagle-import:R0805")
      (libsource (lib "eagle-import") (part "R-EU_R0805"))
    )
    (comp (ref "R26")
      (value "R-EU_R0805")
      (footprint "eagle-import:R0805")
      (libsource (lib "eagle-import") (part "R-EU_R0805"))
    )
    (comp (ref "U$8")
      (value "101X14N330MV4T_X2Y_0603")
      (footprint "eagle-import:101X14N330MV4T_X2Y_0603")
      (libsource (lib "eagle-import") (part "101X14N330MV4T_X2Y_0603"))
    )
    (comp (ref "U$19")
      (value "101X14N330MV4T_X2Y_0603")
      (footprint "eagle-import:101X14N330MV4T_X2Y_0603")
      (libsource (lib "eagle-import") (part "101X14N330MV4T_X2Y_0603"))
    )
    (comp (ref "U2")
      (value "DRV8833RTYT")
      (footprint "eagle-import:QFN65P400X400X80-17N")
      (fields (field (name "MPN") "DRV8833RTYT "))
      (libsource (lib "eagle-import") (part "DRV8833RTYT"))
    )
    (comp (ref "C1")
      (value "10nF")
      (footprint "eagle-import:C0402")
      (libsource (lib "eagle-import") (part "C-EUC0402"))
    )
    (comp (ref "C17")
      (value "100nF")
      (footprint "eagle-import:C0402")
      (libsource (lib "eagle-import") (part "C-EUC0402"))
    )
    (comp (ref "C18")
      (value "2.2uF")
      (footprint "eagle-import:C0603")
      (libsource (lib "eagle-import") (part "C-EUC0603"))
    )
    (comp (ref "C19")
      (value "10nF")
      (footprint "eagle-import:C0402")
      (libsource (lib "eagle-import") (part "C-EUC0402"))
    )
    (comp (ref "C36")
      (value "10nF")
      (footprint "eagle-import:C0402")
      (libsource (lib "eagle-import") (part "C-EUC0402"))
    )
    (comp (ref "M3")
      (value "SFW5R-1STE1LF")
      (footprint "eagle-import:FCI_SFW5R-1STE1LF")
      (libsource (lib "eagle-import") (part "SFW5R-1STE1LF"))
    )
    (comp (ref "M4")
      (value "SFW5R-1STE1LF")
      (footprint "eagle-import:FCI_SFW5R-1STE1LF")
      (libsource (lib "eagle-import") (part "SFW5R-1STE1LF"))
    )
    (comp (ref "R5")
      (value "10K")
      (footprint "eagle-import:R0402")
      (libsource (lib "eagle-import") (part "R-EU_R0402"))
    )
    (comp (ref "R14")
      (value "R-EU_R0805")
      (footprint "eagle-import:R0805")
      (libsource (lib "eagle-import") (part "R-EU_R0805"))
    )
    (comp (ref "R17")
      (value "R-EU_R0805")
      (footprint "eagle-import:R0805")
      (libsource (lib "eagle-import") (part "R-EU_R0805"))
    )
    (comp (ref "U$9")
      (value "101X14N330MV4T_X2Y_0603")
      (footprint "eagle-import:101X14N330MV4T_X2Y_0603")
      (libsource (lib "eagle-import") (part "101X14N330MV4T_X2Y_0603"))
    )
    (comp (ref "U$10")
      (value "101X14N330MV4T_X2Y_0603")
      (footprint "eagle-import:101X14N330MV4T_X2Y_0603")
      (libsource (lib "eagle-import") (part "101X14N330MV4T_X2Y_0603"))
    )
    (comp (ref "U3")
      (value "DRV8833RTYT")
      (footprint "eagle-import:QFN65P400X400X80-17N")
      (fields (field (name "MPN") "DRV8833RTYT "))
      (libsource (lib "eagle-import") (part "DRV8833RTYT"))
    )
  )
  (nets
    (net (code "1") (name "+3V3") (class "Default")
      (node (ref "3.3V") (pin "1") (pinfunction "1_1") (pintype "passive"))
      (node (ref "C11") (pin "1") (pinfunction "1_1") (pintype "passive"))
      (node (ref "C12") (pin "1") (pinfunction "1_1") (pintype "passive"))
      (node (ref "C13") (pin "1") (pinfunction "1_1") (pintype "passive"))
      (node (ref "C20") (pin "1") (pinfunction "1_1") (pintype "passive"))
      (node (ref "C21") (pin "1") (pinfunction "1_1") (pintype "passive"))
      (node (ref "C24") (pin "1") (pinfunction "1_1") (pintype "passive"))
      (node (ref "C28") (pin "1") (pinfunction "1_1") (pintype "passive"))
      (node (ref "C29") (pin "2") (pinfunction "2_2") (pintype "passive"))
      (node (ref "C3") (pin "1") (pinfunction "1_1") (pintype "passive"))
      (node (ref "C35") (pin "1") (pinfunction "1_1") (pintype "passive"))
      (node (ref "C48") (pin "1") (pinfunction "1_1") (pintype "passive"))
      (node (ref "C5") (pin "1") (pinfunction "1_1") (pintype "passive"))
      (node (ref "C50") (pin "1") (pinfunction "1_1") (pintype "passive"))
      (node (ref "C53") (pin "1") (pinfunction "1_1") (pintype "passive"))
      (node (ref "C6") (pin "1") (pinfunction "1_1") (pintype "passive"))
      (node (ref "C8") (pin "1") (pinfunction "1_1") (pintype "passive"))
      (node (ref "D1") (pin "C") (pinfunction "C_C") (pintype "passive"))
      (node (ref "IC2") (pin "17") (pinfunction "VDDIO1_17") (pintype "power_in"))
      (node (ref "IC2") (pin "36") (pinfunction "VDDIO2_36") (pintype "power_in"))
      (node (ref "IC2") (pin "44") (pinfunction "VDDIN_44") (pintype "power_in"))
      (node (ref "J1") (pin "1") (pinfunction "1_1") (pintype "passive"))
      (node (ref "L1") (pin "2") (pinfunction "2_2") (pintype "passive"))
      (node (ref "L2") (pin "2") (pinfunction "2_2") (pintype "passive"))
      (node (ref "LED2") (pin "2") (pinfunction "VDD_2") (pintype "power_in"))
      (node (ref "M1") (pin "2") (pinfunction "2_2") (pintype "passive"))
      (node (ref "M2") (pin "2") (pinfunction "2_2") (pintype "passive"))
      (node (ref "M3") (pin "2") (pinfunction "2_2") (pintype "passive"))
      (node (ref "M4") (pin "2") (pinfunction "2_2") (pintype "passive"))
      (node (ref "R1") (pin "2") (pinfunction "2_2") (pintype "passive"))
      (node (ref "R10") (pin "2") (pinfunction "2_2") (pintype "passive"))
      (node (ref "R13") (pin "2") (pinfunction "2_2") (pintype "passive"))
      (node (ref "R16") (pin "2") (pinfunction "2_2") (pintype "passive"))
      (node (ref "R23") (pin "2") (pinfunction "2_2") (pintype "passive"))
      (node (ref "R24") (pin "2") (pinfunction "2_2") (pintype "passive"))
      (node (ref "R25") (pin "2") (pinfunction "2_2") (pintype "passive"))
      (node (ref "R3") (pin "2") (pinfunction "2_2") (pintype "passive"))
      (node (ref "R4") (pin "1") (pinfunction "1_1") (pintype "passive"))
      (node (ref "R5") (pin "1") (pinfunction "1_1") (pintype "passive"))
      (node (ref "R6") (pin "2") (pinfunction "2_2") (pintype "passive"))
      (node (ref "R9") (pin "1") (pinfunction "1_1") (pintype "passive"))
      (node (ref "TP6") (pin "TP") (pinfunction "TP_TP") (pintype "input"))
      (node (ref "U$15") (pin "2") (pinfunction "VCC+_2") (pintype "bidirectional"))
      (node (ref "U$6") (pin "4") (pinfunction "VCC_4") (pintype "power_in"))
      (node (ref "U$7") (pin "4") (pinfunction "4_4") (pintype "bidirectional"))
      (node (ref "U$7") (pin "4A") (pinfunction "4A_4A") (pintype "bidirectional"))
      (node (ref "U4") (pin "16") (pinfunction "VCC_16") (pintype "power_in"))
      (node (ref "U5") (pin "1") (pinfunction "VDDIO_1") (pintype "bidirectional"))
      (node (ref "U5") (pin "22") (pinfunction "VDD_22") (pintype "bidirectional"))
      (node (ref "U5") (pin "23") (pinfunction "VDD_23") (pintype "bidirectional"))
      (node (ref "U5") (pin "3") (pinfunction "VDDIO_3") (pintype "bidirectional"))
      (node (ref "Z3") (pin "2") (pinfunction "2_2") (pintype "passive"))
    )
    (net (code "2") (name "+12V") (class "Default")
      (node (ref "C14") (pin "1") (pinfunction "1_1") (pintype "passive"))
      (node (ref "C16") (pin "1") (pinfunction "1_1") (pintype "passive"))
      (node (ref "C17") (pin "1") (pinfunction "1_1") (pintype "passive"))
      (node (ref "C19") (pin "1") (pinfunction "1_1") (pintype "passive"))
      (node (ref "C22") (pin "1") (pinfunction "1_1") (pintype "passive"))
      (node (ref "C33") (pin "1") (pinfunction "1_1") (pintype "passive"))
      (node (ref "C4") (pin "1") (pinfunction "1_1") (pintype "passive"))
      (node (ref "F3") (pin "2") (pinfunction "2_2") (pintype "passive"))
      (node (ref "U2") (pin "10") (pinfunction "VM_10") (pintype "power_in"))
      (node (ref "U3") (pin "10") (pinfunction "VM_10") (pintype "power_in"))
    )
    (net (code "3") (name "BROKENOUT") (class "Default")
      (node (ref "IC2") (pin "26") (pinfunction "PA17/I2C/EIC/SCOM1PAD1+/TC2_26") (pintype "bidirectional"))
      (node (ref "J1") (pin "6") (pinfunction "6_6") (pintype "passive"))
    )
    (net (code "4") (name "COMMS_SWITCH") (class "Default")
      (node (ref "IC2") (pin "30") (pinfunction "PA21/EIC/SCOM5PAD3+_30") (pintype "bidirectional"))
      (node (ref "R9") (pin "2") (pinfunction "2_2") (pintype "passive"))
      (node (ref "U4") (pin "4") (pinfunction "1S__4") (pintype "input"))
    )
    (net (code "5") (name "D+") (class "Default")
      (node (ref "IC2") (pin "34") (pinfunction "PA25/EIC/SCOM3PAD3+/TC5_34") (pintype "bidirectional"))
      (node (ref "R21") (pin "2") (pinfunction "2_2") (pintype "passive"))
    )
    (net (code "6") (name "D-") (class "Default")
      (node (ref "IC2") (pin "33") (pinfunction "PA24/EIC/SCOM3PAD2+/TC5_33") (pintype "bidirectional"))
      (node (ref "R22") (pin "2") (pinfunction "2_2") (pintype "passive"))
    )
    (net (code "7") (name "DEN_A{slash}G") (class "Default")
      (node (ref "U5") (pin "13") (pinfunction "DEN_A/G_13") (pintype "bidirectional"))
    )
    (net (code "8") (name "DGI_GPIO0") (class "Default")
      (node (ref "IC2") (pin "22") (pinfunction "PA13/I2C/EIC/SCOM2PAD1+/TC2_22") (pintype "bidirectional"))
    )
    (net (code "9") (name "DRDY_M") (class "Default")
      (node (ref "U5") (pin "9") (pinfunction "DRDY_M_9") (pintype "bidirectional"))
    )
    (net (code "10") (name "EMG_ADC_0") (class "Default")
      (node (ref "IC2") (pin "10") (pinfunction "PA5/EIC/AIN5/SCOM0PAD1/TC0_10") (pintype "bidirectional"))
      (node (ref "R7") (pin "2") (pinfunction "2_2") (pintype "passive"))
    )
    (net (code "11") (name "EMG_ADC_1") (class "Default")
      (node (ref "IC2") (pin "11") (pinfunction "PA6/EIC/AIN6/SCOM0PAD2/TC1_11") (pintype "bidirectional"))
      (node (ref "R8") (pin "2") (pinfunction "2_2") (pintype "passive"))
    )
    (net (code "12") (name "GND") (class "Default")
      (node (ref "C1") (pin "2") (pinfunction "2_2") (pintype "passive"))
      (node (ref "C11") (pin "2") (pinfunction "2_2") (pintype "passive"))
      (node (ref "C12") (pin "2") (pinfunction "2_2") (pintype "passive"))
      (node (ref "C13") (pin "2") (pinfunction "2_2") (pintype "passive"))
      (node (ref "C14") (pin "2") (pinfunction "2_2") (pintype "passive"))
      (node (ref "C15") (pin "2") (pinfunction "2_2") (pintype "passive"))
      (node (ref "C17") (pin "2") (pinfunction "2_2") (pintype "passive"))
      (node (ref "C18") (pin "2") (pinfunction "2_2") (pintype "passive"))
      (node (ref "C2") (pin "2") (pinfunction "2_2") (pintype "passive"))
      (node (ref "C20") (pin "2") (pinfunction "2_2") (pintype "passive"))
      (node (ref "C21") (pin "2") (pinfunction "2_2") (pintype "passive"))
      (node (ref "C22") (pin "2") (pinfunction "2_2") (pintype "passive"))
      (node (ref "C23") (pin "2") (pinfunction "2_2") (pintype "passive"))
      (node (ref "C24") (pin "2") (pinfunction "2_2") (pintype "passive"))
      (node (ref "C25") (pin "2") (pinfunction "2_2") (pintype "passive"))
      (node (ref "C26") (pin "1") (pinfunction "1_1") (pintype "passive"))
      (node (ref "C27") (pin "1") (pinfunction "1_1") (pintype "passive"))
      (node (ref "C28") (pin "2") (pinfunction "2_2") (pintype "passive"))
      (node (ref "C29") (pin "1") (pinfunction "1_1") (pintype "passive"))
      (node (ref "C3") (pin "2") (pinfunction "2_2") (pintype "passive"))
      (node (ref "C30") (pin "2") (pinfunction "2_2") (pintype "passive"))
      (node (ref "C31") (pin "2") (pinfunction "2_2") (pintype "passive"))
      (node (ref "C32") (pin "2") (pinfunction "2_2") (pintype "passive"))
      (node (ref "C33") (pin "2") (pinfunction "2_2") (pintype "passive"))
      (node (ref "C34") (pin "2") (pinfunction "2_2") (pintype "passive"))
      (node (ref "C35") (pin "2") (pinfunction "2_2") (pintype "passive"))
      (node (ref "C36") (pin "2") (pinfunction "2_2") (pintype "passive"))
      (node (ref "C37") (pin "2") (pinfunction "2_2") (pintype "passive"))
      (node (ref "C38") (pin "2") (pinfunction "2_2") (pintype "passive"))
      (node (ref "C4") (pin "2") (pinfunction "2_2") (pintype "passive"))
      (node (ref "C40") (pin "2") (pinfunction "2_2") (pintype "passive"))
      (node (ref "C41") (pin "2") (pinfunction "2_2") (pintype "passive"))
      (node (ref "C48") (pin "2") (pinfunction "2_2") (pintype "passive"))
      (node (ref "C5") (pin "2") (pinfunction "2_2") (pintype "passive"))
      (node (ref "C50") (pin "2") (pinfunction "2_2") (pintype "passive"))
      (node (ref "C51") (pin "2") (pinfunction "2_2") (pintype "passive"))
      (node (ref "C52") (pin "2") (pinfunction "2_2") (pintype "passive"))
      (node (ref "C53") (pin "2") (pinfunction "2_2") (pintype "passive"))
      (node (ref "C6") (pin "2") (pinfunction "2_2") (pintype "passive"))
      (node (ref "C7") (pin "2") (pinfunction "2_2") (pintype "passive"))
      (node (ref "C8") (pin "2") (pinfunction "2_2") (pintype "passive"))
      (node (ref "C9") (pin "2") (pinfunction "2_2") (pintype "passive"))
      (node (ref "GND") (pin "1") (pinfunction "1_1") (pintype "passive"))
      (node (ref "IC2") (pin "18") (pinfunction "GND1_18") (pintype "power_in"))
      (node (ref "IC2") (pin "35") (pinfunction "GND2_35") (pintype "power_in"))
      (node (ref "IC2") (pin "42") (pinfunction "GND3_42") (pintype "power_in"))
      (node (ref "IC2") (pin "5") (pinfunction "GNDANA_5") (pintype "power_in"))
      (node (ref "J1") (pin "8") (pinfunction "8_8") (pintype "passive"))
      (node (ref "LED1") (pin "C") (pinfunction "C_C") (pintype "passive"))
      (node (ref "LED2") (pin "4") (pinfunction "GND_4") (pintype "power_in"))
      (node (ref "M1") (pin "5") (pinfunction "5_5") (pintype "passive"))
      (node (ref "M2") (pin "5") (pinfunction "5_5") (pintype "passive"))
      (node (ref "M3") (pin "5") (pinfunction "5_5") (pintype "passive"))
      (node (ref "M4") (pin "5") (pinfunction "5_5") (pintype "passive"))
      (node (ref "R14") (pin "1") (pinfunction "1_1") (pintype "passive"))
      (node (ref "R17") (pin "1") (pinfunction "1_1") (pintype "passive"))
      (node (ref "R19") (pin "1") (pinfunction "1_1") (pintype "passive"))
      (node (ref "R2") (pin "1") (pinfunction "1_1") (pintype "passive"))
      (node (ref "R26") (pin "1") (pinfunction "1_1") (pintype "passive"))
      (node (ref "R28") (pin "1") (pinfunction "1_1") (pintype "passive"))
      (node (ref "R42") (pin "2") (pinfunction "2_2") (pintype "passive"))
      (node (ref "R56") (pin "2") (pinfunction "2_2") (pintype "passive"))
      (node (ref "R57") (pin "2") (pinfunction "2_2") (pintype "passive"))
      (node (ref "R58") (pin "2") (pinfunction "2_2") (pintype "passive"))
      (node (ref "TP4") (pin "TP") (pinfunction "TP_TP") (pintype "input"))
      (node (ref "U$10") (pin "G") (pinfunction "G_G") (pintype "bidirectional"))
      (node (ref "U$15") (pin "10") (pinfunction "NC2_10") (pintype "bidirectional"))
      (node (ref "U$15") (pin "11") (pinfunction "VCC-_11") (pintype "bidirectional"))
      (node (ref "U$15") (pin "17") (pinfunction "PAD_17") (pintype "bidirectional"))
      (node (ref "U$15") (pin "3") (pinfunction "NC_3") (pintype "bidirectional"))
      (node (ref "U$19") (pin "G") (pinfunction "G_G") (pintype "bidirectional"))
      (node (ref "U$5") (pin "4") (pinfunction "4_4") (pintype "bidirectional"))
      (node (ref "U$6") (pin "2") (pinfunction "VSS_2") (pintype "passive"))
      (node (ref "U$6") (pin "5") (pinfunction "WP_5") (pintype "input"))
      (node (ref "U$7") (pin "1") (pinfunction "1_1") (pintype "bidirectional"))
      (node (ref "U$8") (pin "G") (pinfunction "G_G") (pintype "bidirectional"))
      (node (ref "U$9") (pin "G") (pinfunction "G_G") (pintype "bidirectional"))
      (node (ref "U1") (pin "4") (pinfunction "AGND_4") (pintype "power_in"))
      (node (ref "U1") (pin "5") (pinfunction "SYNC_5") (pintype "passive"))
      (node (ref "U1") (pin "8") (pinfunction "PGND_8") (pintype "power_in"))
      (node (ref "U1") (pin "9") (pinfunction "EPAD_9") (pintype "passive"))
      (node (ref "U2") (pin "11") (pinfunction "GND_11") (pintype "passive"))
      (node (ref "U2") (pin "17") (pinfunction "EPAD_17") (pintype "passive"))
      (node (ref "U3") (pin "11") (pinfunction "GND_11") (pintype "passive"))
      (node (ref "U3") (pin "17") (pinfunction "EPAD_17") (pintype "passive"))
      (node (ref "U4") (pin "8") (pinfunction "GND_8") (pintype "passive"))
      (node (ref "U5") (pin "14") (pinfunction "RES_14") (pintype "bidirectional"))
      (node (ref "U5") (pin "15") (pinfunction "RES_15") (pintype "bidirectional"))
      (node (ref "U5") (pin "16") (pinfunction "RES_16") (pintype "bidirectional"))
      (node (ref "U5") (pin "17") (pinfunction "RES_17") (pintype "bidirectional"))
      (node (ref "U5") (pin "18") (pinfunction "RES_18") (pintype "bidirectional"))
      (node (ref "U5") (pin "19") (pinfunction "GND_19") (pintype "bidirectional"))
      (node (ref "U5") (pin "20") (pinfunction "GND_20") (pintype "bidirectional"))
      (node (ref "USB1") (pin "P4") (pinfunction "USBID_P4") (pintype "bidirectional"))
      (node (ref "USB1") (pin "P5") (pinfunction "GND_P5") (pintype "bidirectional"))
      (node (ref "Z1") (pin "1") (pinfunction "1_1") (pintype "passive"))
      (node (ref "Z2") (pin "1") (pinfunction "1_1") (pintype "passive"))
      (node (ref "Z3") (pin "1") (pinfunction "1_1") (pintype "passive"))
      (node (ref "Z4") (pin "1") (pinfunction "1_1") (pintype "passive"))
      (node (ref "Z5") (pin "1") (pinfunction "1_1") (pintype "passive"))
    )
    (net (code "13") (name "INT1_A{slash}G") (class "Default")
      (node (ref "U5") (pin "11") (pinfunction "INT1_A/G_11") (pintype "bidirectional"))
    )
    (net (code "14") (name "INT2_A{slash}G") (class "Default")
      (node (ref "U5") (pin "12") (pinfunction "INT2_A/G_12") (pintype "bidirectional"))
    )
    (net (code "15") (name "INT_M") (class "Default")
      (node (ref "U5") (pin "10") (pinfunction "INT_M_10") (pintype "bidirectional"))
    )
    (net (code "16") (name "M1-ISENSE") (class "Default")
      (node (ref "R19") (pin "2") (pinfunction "2_2") (pintype "passive"))
      (node (ref "R37") (pin "2") (pinfunction "2_2") (pintype "passive"))
      (node (ref "U2") (pin "1") (pinfunction "AISEN_1") (pintype "bidirectional"))
    )
    (net (code "17") (name "M1-ISENSE-OUT") (class "Default")
      (node (ref "IC2") (pin "15") (pinfunction "PA10/EIC/AIN18/SCOM2PAD2+/TC1_15") (pintype "bidirectional"))
      (node (ref "R47") (pin "1") (pinfunction "1_1") (pintype "passive"))
      (node (ref "U$15") (pin "15") (pinfunction "1OUT_15") (pintype "bidirectional"))
    )
    (net (code "18") (name "M2-ISENSE") (class "Default")
      (node (ref "R26") (pin "2") (pinfunction "2_2") (pintype "passive"))
      (node (ref "R29") (pin "2") (pinfunction "2_2") (pintype "passive"))
      (node (ref "U2") (pin "4") (pinfunction "BISEN_4") (pintype "bidirectional"))
    )
    (net (code "19") (name "M2-ISENSE-OUT") (class "Default")
      (node (ref "IC2") (pin "48") (pinfunction "PB3/EIC/AIN11/SCOM5PAD1_48") (pintype "bidirectional"))
      (node (ref "R48") (pin "1") (pinfunction "1_1") (pintype "passive"))
      (node (ref "U$15") (pin "6") (pinfunction "2OUT_6") (pintype "bidirectional"))
    )
    (net (code "20") (name "M3-ISENSE") (class "Default")
      (node (ref "R14") (pin "2") (pinfunction "2_2") (pintype "passive"))
      (node (ref "R39") (pin "2") (pinfunction "2_2") (pintype "passive"))
      (node (ref "U3") (pin "1") (pinfunction "AISEN_1") (pintype "bidirectional"))
    )
    (net (code "21") (name "M3-ISENSE-OUT") (class "Default")
      (node (ref "IC2") (pin "47") (pinfunction "PB2/EIC/AIN10/SCOM5PAD0_47") (pintype "bidirectional"))
      (node (ref "R49") (pin "1") (pinfunction "1_1") (pintype "passive"))
      (node (ref "U$15") (pin "7") (pinfunction "3OUT_7") (pintype "bidirectional"))
    )
    (net (code "22") (name "M4-ISENSE") (class "Default")
      (node (ref "R17") (pin "2") (pinfunction "2_2") (pintype "passive"))
      (node (ref "R46") (pin "2") (pinfunction "2_2") (pintype "passive"))
      (node (ref "U3") (pin "4") (pinfunction "BISEN_4") (pintype "bidirectional"))
    )
    (net (code "23") (name "M4-ISENSE-OUT") (class "Default")
      (node (ref "IC2") (pin "16") (pinfunction "PA11/EIC/AIN19/SCOM2PAD3+/TC1_16") (pintype "bidirectional"))
      (node (ref "R50") (pin "1") (pinfunction "1_1") (pintype "passive"))
      (node (ref "U$15") (pin "14") (pinfunction "4OUT_14") (pintype "bidirectional"))
    )
    (net (code "24") (name "MOTOR1_CLOSE") (class "Default")
      (node (ref "IC2") (pin "14") (pinfunction "PA9/I2C/EIC/AIN17/SCOM2PAD1+/TC0_14") (pintype "bidirectional"))
      (node (ref "U2") (pin "13") (pinfunction "AIN2_13") (pintype "input"))
    )
    (net (code "25") (name "MOTOR1_OPEN") (class "Default")
      (node (ref "IC2") (pin "13") (pinfunction "PA8/I2C/AIN16/SCOM2PAD0+/TC0_13") (pintype "bidirectional"))
      (node (ref "U2") (pin "14") (pinfunction "AIN1_14") (pintype "input"))
    )
    (net (code "26") (name "MOTOR1_SENSE") (class "Default")
      (node (ref "C37") (pin "1") (pinfunction "1_1") (pintype "passive"))
      (node (ref "IC2") (pin "3") (pinfunction "PA2/EIC/AIN0_3") (pintype "bidirectional"))
      (node (ref "M1") (pin "1") (pinfunction "1_1") (pintype "passive"))
    )
    (net (code "27") (name "MOTOR2_CLOSE") (class "Default")
      (node (ref "IC2") (pin "27") (pinfunction "PA18/EIC/SCOM1PAD2+/TC3_27") (pintype "bidirectional"))
      (node (ref "U2") (pin "8") (pinfunction "BIN2_8") (pintype "input"))
    )
    (net (code "28") (name "MOTOR2_OPEN") (class "Default")
      (node (ref "IC2") (pin "25") (pinfunction "PA16/I2C/EIC/SCOM1PAD0+/TC2_25") (pintype "bidirectional"))
      (node (ref "U2") (pin "7") (pinfunction "BIN1_7") (pintype "input"))
    )
    (net (code "29") (name "MOTOR2_SENSE") (class "Default")
      (node (ref "C38") (pin "1") (pinfunction "1_1") (pintype "passive"))
      (node (ref "IC2") (pin "7") (pinfunction "PB8/EIC/AIN2/SCOM4PAD0/TC4_7") (pintype "bidirectional"))
      (node (ref "M2") (pin "1") (pinfunction "1_1") (pintype "passive"))
    )
    (net (code "30") (name "MOTOR3_CLOSE") (class "Default")
      (node (ref "IC2") (pin "28") (pinfunction "PA19/EIC/SCOM1PAD3+/TC3_28") (pintype "bidirectional"))
      (node (ref "U3") (pin "13") (pinfunction "AIN2_13") (pintype "input"))
    )
    (net (code "31") (name "MOTOR3_OPEN") (class "Default")
      (node (ref "IC2") (pin "24") (pinfunction "PA15/XOUT/EIC/SCOM2PAD3+/TC3_24") (pintype "bidirectional"))
      (node (ref "U3") (pin "14") (pinfunction "AIN1_14") (pintype "input"))
    )
    (net (code "32") (name "MOTOR3_SENSE") (class "Default")
      (node (ref "C1") (pin "1") (pinfunction "1_1") (pintype "passive"))
      (node (ref "IC2") (pin "8") (pinfunction "PB9/EIC/AIN3/SCOM4PAD1//TC4_8") (pintype "bidirectional"))
      (node (ref "M3") (pin "1") (pinfunction "1_1") (pintype "passive"))
    )
    (net (code "33") (name "MOTOR4_CLOSE") (class "Default")
      (node (ref "IC2") (pin "12") (pinfunction "PA7/EIC/AIN7/SCOM0PAD3/TC1_12") (pintype "bidirectional"))
      (node (ref "U3") (pin "8") (pinfunction "BIN2_8") (pintype "input"))
    )
    (net (code "34") (name "MOTOR4_OPEN") (class "Default")
      (node (ref "IC2") (pin "29") (pinfunction "PA20/EIC/SCOM5PAD2+_29") (pintype "bidirectional"))
      (node (ref "U3") (pin "7") (pinfunction "BIN1_7") (pintype "input"))
    )
    (net (code "35") (name "MOTOR4_SENSE") (class "Default")
      (node (ref "C36") (pin "1") (pinfunction "1_1") (pintype "passive"))
      (node (ref "IC2") (pin "9") (pinfunction "PA4/EIC/REF/AIN4/SCOM0PAD0/TC0_9") (pintype "bidirectional"))
      (node (ref "M4") (pin "1") (pinfunction "1_1") (pintype "passive"))
    )
    (net (code "36") (name "NEOPIXEL") (class "Default")
      (node (ref "IC2") (pin "23") (pinfunction "PA14/XIN/EIC/SCOM2PAD2+/TC3_23") (pintype "bidirectional"))
      (node (ref "LED2") (pin "1") (pinfunction "DI_1") (pintype "input"))
    )
    (net (code "37") (name "NEOPIXEL_OUT") (class "Default")
      (node (ref "J1") (pin "7") (pinfunction "7_7") (pintype "passive"))
      (node (ref "LED2") (pin "3") (pinfunction "DO_3") (pintype "output"))
    )
    (net (code "38") (name "Net-(C34-Pad1)") (class "Default")
      (node (ref "C34") (pin "1") (pinfunction "1_1") (pintype "passive"))
      (node (ref "F2") (pin "1") (pinfunction "1_1") (pintype "passive"))
      (node (ref "F3") (pin "1") (pinfunction "1_1") (pintype "passive"))
      (node (ref "U$5") (pin "2") (pinfunction "2_2") (pintype "bidirectional"))
    )
    (net (code "39") (name "Net-(CN1-GND)") (class "Default")
      (node (ref "C10") (pin "2") (pinfunction "2_2") (pintype "passive"))
      (node (ref "CN1") (pin "GND") (pinfunction "GNDBREAK_GND") (pintype "power_in"))
      (node (ref "CN1") (pin "GNDBREAK") (pinfunction "GND_GNDBREAK") (pintype "power_in"))
      (node (ref "U$5") (pin "3") (pinfunction "3_3") (pintype "bidirectional"))
    )
    (net (code "40") (name "Net-(CN1-PWR)") (class "Default")
      (node (ref "C10") (pin "1") (pinfunction "1_1") (pintype "passive"))
      (node (ref "CN1") (pin "PWR1") (pinfunction "PWR_PWR1") (pintype "power_in"))
      (node (ref "U$5") (pin "1") (pinfunction "1_1") (pintype "bidirectional"))
    )
    (net (code "41") (name "Net-(IC2-VDDANA)") (class "Default")
      (node (ref "C25") (pin "1") (pinfunction "1_1") (pintype "passive"))
      (node (ref "IC2") (pin "6") (pinfunction "VDDANA_6") (pintype "power_in"))
      (node (ref "L2") (pin "1") (pinfunction "1_1") (pintype "passive"))
    )
    (net (code "42") (name "Net-(LED1-PadA)") (class "Default")
      (node (ref "LED1") (pin "A") (pinfunction "A_A") (pintype "passive"))
      (node (ref "R10") (pin "1") (pinfunction "1_1") (pintype "passive"))
    )
    (net (code "43") (name "Net-(U$15A-1+)") (class "Default")
      (node (ref "R37") (pin "1") (pinfunction "1_1") (pintype "passive"))
      (node (ref "U$15") (pin "1") (pinfunction "1+_1") (pintype "bidirectional"))
    )
    (net (code "44") (name "Net-(U$15A-1-)") (class "Default")
      (node (ref "R47") (pin "2") (pinfunction "2_2") (pintype "passive"))
      (node (ref "R57") (pin "1") (pinfunction "1_1") (pintype "passive"))
      (node (ref "U$15") (pin "16") (pinfunction "1-_16") (pintype "bidirectional"))
    )
    (net (code "45") (name "Net-(U$15B-2+)") (class "Default")
      (node (ref "R29") (pin "1") (pinfunction "1_1") (pintype "passive"))
      (node (ref "U$15") (pin "4") (pinfunction "2+_4") (pintype "bidirectional"))
    )
    (net (code "46") (name "Net-(U$15B-2-)") (class "Default")
      (node (ref "R48") (pin "2") (pinfunction "2_2") (pintype "passive"))
      (node (ref "R58") (pin "1") (pinfunction "1_1") (pintype "passive"))
      (node (ref "U$15") (pin "5") (pinfunction "2-_5") (pintype "bidirectional"))
    )
    (net (code "47") (name "Net-(U$15C-3+)") (class "Default")
      (node (ref "R39") (pin "1") (pinfunction "1_1") (pintype "passive"))
      (node (ref "U$15") (pin "9") (pinfunction "3+_9") (pintype "bidirectional"))
    )
    (net (code "48") (name "Net-(U$15C-3-)") (class "Default")
      (node (ref "R42") (pin "1") (pinfunction "1_1") (pintype "passive"))
      (node (ref "R49") (pin "2") (pinfunction "2_2") (pintype "passive"))
      (node (ref "U$15") (pin "8") (pinfunction "3-_8") (pintype "bidirectional"))
    )
    (net (code "49") (name "Net-(U$15D-4+)") (class "Default")
      (node (ref "R46") (pin "1") (pinfunction "1_1") (pintype "passive"))
      (node (ref "U$15") (pin "12") (pinfunction "4+_12") (pintype "bidirectional"))
    )
    (net (code "50") (name "Net-(U$15D-4-)") (class "Default")
      (node (ref "R50") (pin "2") (pinfunction "2_2") (pintype "passive"))
      (node (ref "R56") (pin "1") (pinfunction "1_1") (pintype "passive"))
      (node (ref "U$15") (pin "13") (pinfunction "4-_13") (pintype "bidirectional"))
    )
    (net (code "51") (name "Net-(U1-INH_(EN))") (class "Default")
      (node (ref "C2") (pin "1") (pinfunction "1_1") (pintype "passive"))
      (node (ref "C7") (pin "1") (pinfunction "1_1") (pintype "passive"))
      (node (ref "C9") (pin "1") (pinfunction "1_1") (pintype "passive"))
      (node (ref "F2") (pin "2") (pinfunction "2_2") (pintype "passive"))
      (node (ref "U1") (pin "1") (pinfunction "VIN_A_1") (pintype "input"))
      (node (ref "U1") (pin "2") (pinfunction "INH_(EN)_2") (pintype "passive"))
      (node (ref "U1") (pin "6") (pinfunction "VIN_SW_6") (pintype "passive"))
    )
    (net (code "52") (name "Net-(U1-SW)") (class "Default")
      (node (ref "L1") (pin "1") (pinfunction "1_1") (pintype "passive"))
      (node (ref "U1") (pin "7") (pinfunction "SW_7") (pintype "passive"))
    )
    (net (code "53") (name "Net-(U1-VFB)") (class "Default")
      (node (ref "R1") (pin "1") (pinfunction "1_1") (pintype "passive"))
      (node (ref "R2") (pin "2") (pinfunction "2_2") (pintype "passive"))
      (node (ref "U1") (pin "3") (pinfunction "VFB_3") (pintype "passive"))
    )
    (net (code "54") (name "Net-(U2-AOUT1)") (class "Default")
      (node (ref "M1") (pin "3") (pinfunction "3_3") (pintype "passive"))
      (node (ref "U$19") (pin "A") (pinfunction "A_A") (pintype "bidirectional"))
      (node (ref "U2") (pin "16") (pinfunction "AOUT1_16") (pintype "output"))
    )
    (net (code "55") (name "Net-(U2-AOUT2)") (class "Default")
      (node (ref "M1") (pin "4") (pinfunction "4_4") (pintype "passive"))
      (node (ref "U$19") (pin "B") (pinfunction "B_B") (pintype "bidirectional"))
      (node (ref "U2") (pin "2") (pinfunction "AOUT2_2") (pintype "output"))
    )
    (net (code "56") (name "Net-(U2-BOUT1)") (class "Default")
      (node (ref "M2") (pin "4") (pinfunction "4_4") (pintype "passive"))
      (node (ref "U$8") (pin "B") (pinfunction "B_B") (pintype "bidirectional"))
      (node (ref "U2") (pin "5") (pinfunction "BOUT1_5") (pintype "bidirectional"))
    )
    (net (code "57") (name "Net-(U2-BOUT2)") (class "Default")
      (node (ref "M2") (pin "3") (pinfunction "3_3") (pintype "passive"))
      (node (ref "U$8") (pin "A") (pinfunction "A_A") (pintype "bidirectional"))
      (node (ref "U2") (pin "3") (pinfunction "BOUT2_3") (pintype "output"))
    )
    (net (code "58") (name "Net-(U2-NSLEEP)") (class "Default")
      (node (ref "R4") (pin "2") (pinfunction "2_2") (pintype "passive"))
      (node (ref "U2") (pin "15") (pinfunction "NSLEEP_15") (pintype "input"))
    )
    (net (code "59") (name "Net-(U2-VCP)") (class "Default")
      (node (ref "C16") (pin "2") (pinfunction "2_2") (pintype "passive"))
      (node (ref "U2") (pin "9") (pinfunction "VCP_9") (pintype "bidirectional"))
    )
    (net (code "60") (name "Net-(U2-VINT)") (class "Default")
      (node (ref "C15") (pin "1") (pinfunction "1_1") (pintype "passive"))
      (node (ref "U2") (pin "12") (pinfunction "VINT_12") (pintype "power_in"))
    )
    (net (code "61") (name "Net-(U3-AOUT1)") (class "Default")
      (node (ref "M3") (pin "3") (pinfunction "3_3") (pintype "passive"))
      (node (ref "U$9") (pin "A") (pinfunction "A_A") (pintype "bidirectional"))
      (node (ref "U3") (pin "16") (pinfunction "AOUT1_16") (pintype "output"))
    )
    (net (code "62") (name "Net-(U3-AOUT2)") (class "Default")
      (node (ref "M3") (pin "4") (pinfunction "4_4") (pintype "passive"))
      (node (ref "U$9") (pin "B") (pinfunction "B_B") (pintype "bidirectional"))
      (node (ref "U3") (pin "2") (pinfunction "AOUT2_2") (pintype "output"))
    )
    (net (code "63") (name "Net-(U3-BOUT1)") (class "Default")
      (node (ref "M4") (pin "4") (pinfunction "4_4") (pintype "passive"))
      (node (ref "U$10") (pin "B") (pinfunction "B_B") (pintype "bidirectional"))
      (node (ref "U3") (pin "5") (pinfunction "BOUT1_5") (pintype "bidirectional"))
    )
    (net (code "64") (name "Net-(U3-BOUT2)") (class "Default")
      (node (ref "M4") (pin "3") (pinfunction "3_3") (pintype "passive"))
      (node (ref "U$10") (pin "A") (pinfunction "A_A") (pintype "bidirectional"))
      (node (ref "U3") (pin "3") (pinfunction "BOUT2_3") (pintype "output"))
    )
    (net (code "65") (name "Net-(U3-NSLEEP)") (class "Default")
      (node (ref "R5") (pin "2") (pinfunction "2_2") (pintype "passive"))
      (node (ref "U3") (pin "15") (pinfunction "NSLEEP_15") (pintype "input"))
    )
    (net (code "66") (name "Net-(U3-VCP)") (class "Default")
      (node (ref "C19") (pin "2") (pinfunction "2_2") (pintype "passive"))
      (node (ref "U3") (pin "9") (pinfunction "VCP_9") (pintype "bidirectional"))
    )
    (net (code "67") (name "Net-(U3-VINT)") (class "Default")
      (node (ref "C18") (pin "1") (pinfunction "1_1") (pintype "passive"))
      (node (ref "U3") (pin "12") (pinfunction "VINT_12") (pintype "power_in"))
    )
    (net (code "68") (name "Net-(U4-1Y1_)") (class "Default")
      (node (ref "R7") (pin "1") (pinfunction "1_1") (pintype "passive"))
      (node (ref "U4") (pin "1") (pinfunction "1Y1__1") (pintype "bidirectional"))
    )
    (net (code "69") (name "Net-(U4-1Z_)") (class "Default")
      (node (ref "U$7") (pin "2") (pinfunction "2_2") (pintype "bidirectional"))
      (node (ref "U4") (pin "2") (pinfunction "1Z__2") (pintype "bidirectional"))
      (node (ref "Z5") (pin "2") (pinfunction "2_2") (pintype "passive"))
    )
    (net (code "70") (name "Net-(U4-2Y1_)") (class "Default")
      (node (ref "R8") (pin "1") (pinfunction "1_1") (pintype "passive"))
      (node (ref "U4") (pin "5") (pinfunction "2Y1__5") (pintype "bidirectional"))
    )
    (net (code "71") (name "Net-(U4-2Z_)") (class "Default")
      (node (ref "U$7") (pin "3") (pinfunction "3_3") (pintype "bidirectional"))
      (node (ref "U4") (pin "6") (pinfunction "2Z__6") (pintype "bidirectional"))
      (node (ref "Z4") (pin "2") (pinfunction "2_2") (pintype "passive"))
    )
    (net (code "72") (name "Net-(U5-C1)") (class "Default")
      (node (ref "C51") (pin "1") (pinfunction "1_1") (pintype "passive"))
      (node (ref "U5") (pin "24") (pinfunction "C1_24") (pintype "bidirectional"))
    )
    (net (code "73") (name "Net-(U5-CAP)") (class "Default")
      (node (ref "C52") (pin "1") (pinfunction "1_1") (pintype "passive"))
      (node (ref "U5") (pin "21") (pinfunction "CAP_21") (pintype "bidirectional"))
    )
    (net (code "74") (name "Net-(U5-CS_A{slash}G)") (class "Default")
      (node (ref "R23") (pin "1") (pinfunction "1_1") (pintype "passive"))
      (node (ref "U5") (pin "7") (pinfunction "CS_A/G_7") (pintype "bidirectional"))
    )
    (net (code "75") (name "Net-(U5-CS_M)") (class "Default")
      (node (ref "R24") (pin "1") (pinfunction "1_1") (pintype "passive"))
      (node (ref "U5") (pin "8") (pinfunction "CS_M_8") (pintype "bidirectional"))
    )
    (net (code "76") (name "Net-(U5-SDO_A{slash}G)") (class "Default")
      (node (ref "R25") (pin "1") (pinfunction "1_1") (pintype "passive"))
      (node (ref "U5") (pin "5") (pinfunction "SDO_A/G_5") (pintype "bidirectional"))
    )
    (net (code "77") (name "Net-(U5-SDO_M)") (class "Default")
      (node (ref "R6") (pin "1") (pinfunction "1_1") (pintype "passive"))
      (node (ref "U5") (pin "6") (pinfunction "SDO_M_6") (pintype "bidirectional"))
    )
    (net (code "78") (name "Net-(USB1B-D+)") (class "Default")
      (node (ref "C40") (pin "1") (pinfunction "1_1") (pintype "passive"))
      (node (ref "R21") (pin "1") (pinfunction "1_1") (pintype "passive"))
      (node (ref "USB1") (pin "P3") (pinfunction "D+_P3") (pintype "bidirectional"))
      (node (ref "Z1") (pin "2") (pinfunction "2_2") (pintype "passive"))
    )
    (net (code "79") (name "Net-(USB1B-D-)") (class "Default")
      (node (ref "C41") (pin "1") (pinfunction "1_1") (pintype "passive"))
      (node (ref "R22") (pin "1") (pinfunction "1_1") (pintype "passive"))
      (node (ref "USB1") (pin "P2") (pinfunction "D-_P2") (pintype "bidirectional"))
      (node (ref "Z2") (pin "2") (pinfunction "2_2") (pintype "passive"))
    )
    (net (code "80") (name "PA03_AREFA") (class "Default")
      (node (ref "C31") (pin "1") (pinfunction "1_1") (pintype "passive"))
      (node (ref "C32") (pin "1") (pinfunction "1_1") (pintype "passive"))
      (node (ref "IC2") (pin "4") (pinfunction "PA3/EIC/REF/AIN1_4") (pintype "bidirectional"))
    )
    (net (code "81") (name "PA27_TX_LED") (class "Default")
      (node (ref "IC2") (pin "39") (pinfunction "PA27/EIC_39") (pintype "bidirectional"))
    )
    (net (code "82") (name "PA28_USB_HOST_EN") (class "Default")
      (node (ref "IC2") (pin "41") (pinfunction "PA28/EIC_41") (pintype "bidirectional"))
      (node (ref "R28") (pin "2") (pinfunction "2_2") (pintype "passive"))
    )
    (net (code "83") (name "PA30_SWCLK") (class "Default")
      (node (ref "IC2") (pin "45") (pinfunction "PA30/EIC/SCOM1PAD2/TC1_45") (pintype "bidirectional"))
      (node (ref "TP2") (pin "TP") (pinfunction "TP_TP") (pintype "input"))
    )
    (net (code "84") (name "PA31_SWDIO") (class "Default")
      (node (ref "IC2") (pin "46") (pinfunction "PA31/EIC/SCOM1PAD3/TC1_46") (pintype "bidirectional"))
      (node (ref "TP5") (pin "TP") (pinfunction "TP_TP") (pintype "input"))
    )
    (net (code "85") (name "PB10_S4_SPI_MOSI") (class "Default")
      (node (ref "IC2") (pin "19") (pinfunction "PB10/EIC/SCOM4PAD2/TC5_19") (pintype "bidirectional"))
    )
    (net (code "86") (name "PB11_S4_SPI_SCK") (class "Default")
      (node (ref "IC2") (pin "20") (pinfunction "PB11/EIC/SCOM4PAD3/TC5_20") (pintype "bidirectional"))
    )
    (net (code "87") (name "PB12_S4_SPI_MISO") (class "Default")
      (node (ref "IC2") (pin "21") (pinfunction "PA12/I2C/EIC/SCOM2PAD0+/TC2_21") (pintype "bidirectional"))
    )
    (net (code "88") (name "RESET") (class "Default")
      (node (ref "D1") (pin "A") (pinfunction "A_A") (pintype "passive"))
      (node (ref "R13") (pin "1") (pinfunction "1_1") (pintype "passive"))
      (node (ref "R15") (pin "2") (pinfunction "2_2") (pintype "passive"))
      (node (ref "TP1") (pin "TP") (pinfunction "TP_TP") (pintype "input"))
    )
    (net (code "89") (name "RXD") (class "Default")
      (node (ref "IC2") (pin "38") (pinfunction "PB23/EIC/SCOM5PAD3_38") (pintype "bidirectional"))
      (node (ref "J1") (pin "3") (pinfunction "3_3") (pintype "passive"))
    )
    (net (code "90") (name "SCL") (class "Default")
      (node (ref "IC2") (pin "32") (pinfunction "PA23/I2C/EIC/SCOM5PAD1+/TC4_32") (pintype "bidirectional"))
      (node (ref "J1") (pin "4") (pinfunction "4_4") (pintype "passive"))
      (node (ref "R16") (pin "1") (pinfunction "1_1") (pintype "passive"))
      (node (ref "U$6") (pin "1") (pinfunction "SCL_1") (pintype "input"))
      (node (ref "U4") (pin "3") (pinfunction "1Y0__3") (pintype "bidirectional"))
      (node (ref "U5") (pin "2") (pinfunction "SCL/SPC_2") (pintype "bidirectional"))
    )
    (net (code "91") (name "SDA") (class "Default")
      (node (ref "IC2") (pin "31") (pinfunction "PA22/I2C/EIC/SCOM5PAD0+/TC4_31") (pintype "bidirectional"))
      (node (ref "J1") (pin "5") (pinfunction "5_5") (pintype "passive"))
      (node (ref "R3") (pin "1") (pinfunction "1_1") (pintype "passive"))
      (node (ref "U$6") (pin "3") (pinfunction "SDA_3") (pintype "bidirectional"))
      (node (ref "U4") (pin "7") (pinfunction "2Y0_7") (pintype "bidirectional"))
      (node (ref "U5") (pin "4") (pinfunction "SDA/SDI/SDO_4") (pintype "bidirectional"))
    )
    (net (code "92") (name "TARGET_RESET_EDBG") (class "Default")
      (node (ref "C30") (pin "1") (pinfunction "1_1") (pintype "passive"))
      (node (ref "IC2") (pin "40") (pinfunction "RESETN_40") (pintype "bidirectional"))
      (node (ref "R15") (pin "1") (pinfunction "1_1") (pintype "passive"))
    )
    (net (code "93") (name "TXD") (class "Default")
      (node (ref "IC2") (pin "37") (pinfunction "PB22/EIC/SCOM5PAD2_37") (pintype "bidirectional"))
      (node (ref "J1") (pin "2") (pinfunction "2_2") (pintype "passive"))
    )
    (net (code "94") (name "VDDCORE") (class "Default")
      (node (ref "C23") (pin "1") (pinfunction "1_1") (pintype "passive"))
      (node (ref "IC2") (pin "43") (pinfunction "VDDCORE1_43") (pintype "input"))
    )
    (net (code "95") (name "XTAL_IN") (class "Default")
      (node (ref "C26") (pin "2") (pinfunction "2_2") (pintype "passive"))
      (node (ref "IC2") (pin "1") (pinfunction "PA0/XIN32/EIC/SCOM1PAD0/TC2_1") (pintype "bidirectional"))
      (node (ref "Y1") (pin "P$2") (pinfunction "2_P$2") (pintype "bidirectional"))
    )
    (net (code "96") (name "XTAL_OUT") (class "Default")
      (node (ref "C27") (pin "2") (pinfunction "2_2") (pintype "passive"))
      (node (ref "IC2") (pin "2") (pinfunction "PA1/XOUT32/EIC/SCOM1PAD1/TC2_2") (pintype "bidirectional"))
      (node (ref "Y1") (pin "P$1") (pinfunction "1_P$1") (pintype "bidirectional"))
    )
    (net (code "97") (name "unconnected-(TP3-PadTP)") (class "Default")
      (node (ref "TP3") (pin "TP") (pinfunction "TP_TP") (pintype "input"))
    )
    (net (code "98") (name "unconnected-(U2-NFAULT-Pad6)") (class "Default")
      (node (ref "U2") (pin "6") (pinfunction "NFAULT_6") (pintype "output"))
    )
    (net (code "99") (name "unconnected-(U3-NFAULT-Pad6)") (class "Default")
      (node (ref "U3") (pin "6") (pinfunction "NFAULT_6") (pintype "output"))
    )
    (net (code "100") (name "unconnected-(U4-2S-Pad12)") (class "Default")
      (node (ref "U4") (pin "12") (pinfunction "2S_12") (pintype "input"))
    )
    (net (code "101") (name "unconnected-(U4-3Y0-Pad11)") (class "Default")
      (node (ref "U4") (pin "11") (pinfunction "3Y0_11") (pintype "bidirectional"))
    )
    (net (code "102") (name "unconnected-(U4-3Y1-Pad9)") (class "Default")
      (node (ref "U4") (pin "9") (pinfunction "3Y1_9") (pintype "bidirectional"))
    )
    (net (code "103") (name "unconnected-(U4-3Z-Pad10)") (class "Default")
      (node (ref "U4") (pin "10") (pinfunction "3Z_10") (pintype "bidirectional"))
    )
    (net (code "104") (name "unconnected-(U4-4Y0-Pad15)") (class "Default")
      (node (ref "U4") (pin "15") (pinfunction "4Y0_15") (pintype "bidirectional"))
    )
    (net (code "105") (name "unconnected-(U4-4Y1-Pad13)") (class "Default")
      (node (ref "U4") (pin "13") (pinfunction "4Y1_13") (pintype "bidirectional"))
    )
    (net (code "106") (name "unconnected-(U4-4Z-Pad14)") (class "Default")
      (node (ref "U4") (pin "14") (pinfunction "4Z_14") (pintype "bidirectional"))
    )
    (net (code "107") (name "unconnected-(USB1B-VUSB-PadP1)") (class "Default")
      (node (ref "USB1") (pin "P1") (pinfunction "VUSB_P1") (pintype "bidirectional"))
    )
  )
)
